# harp_timestamp_generator_Gen3.net
KiCad netlist of a schematic drawn in EAGLE
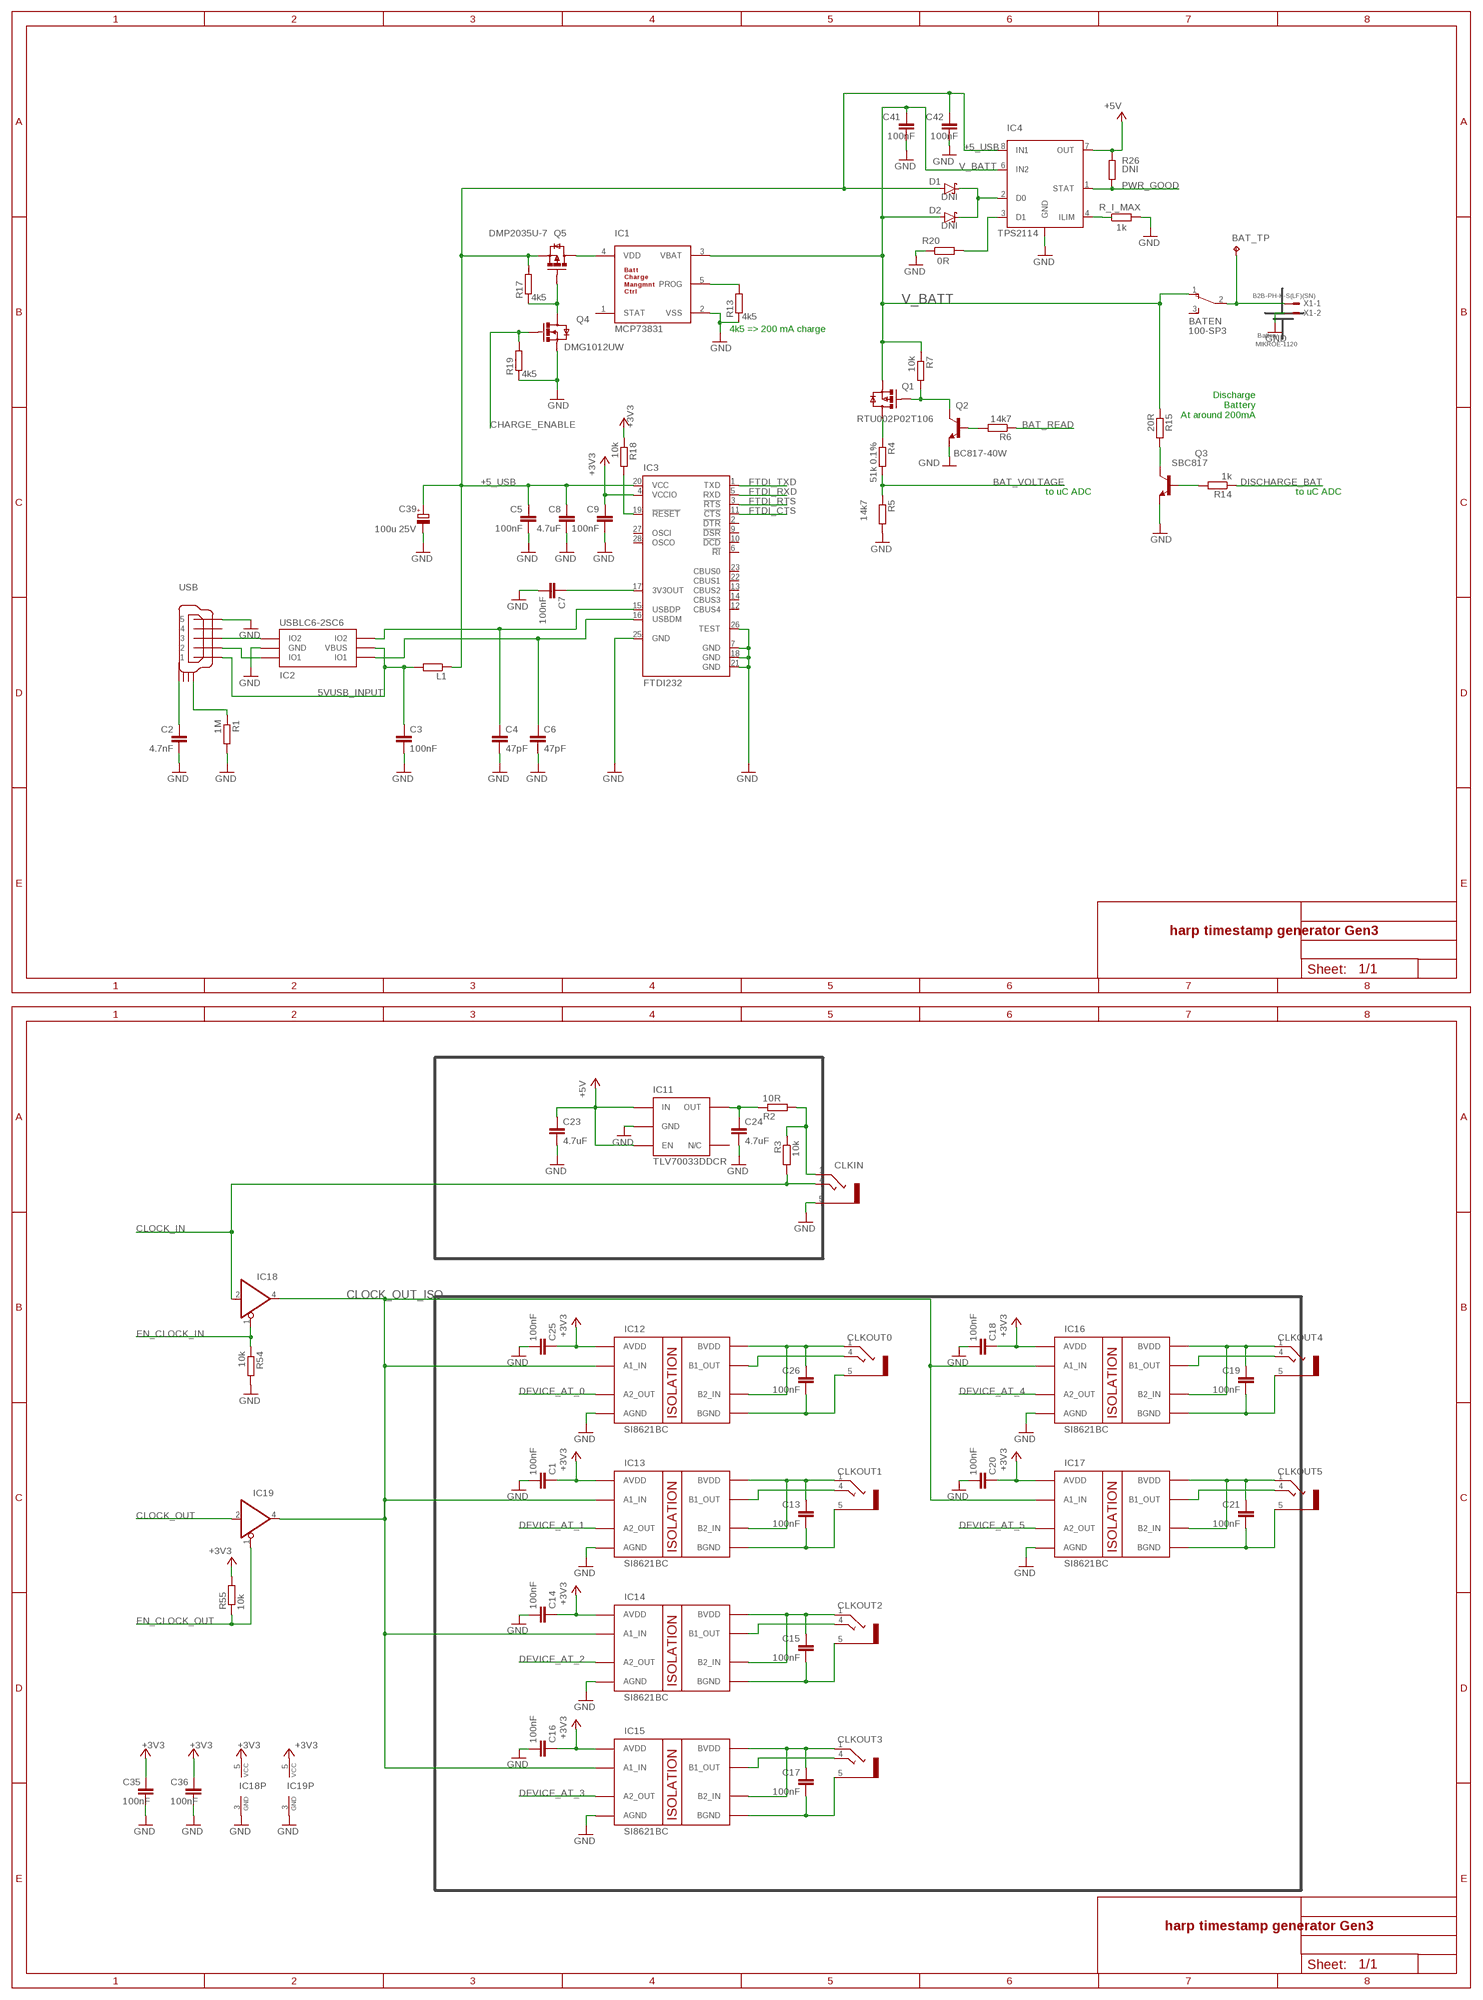
[diagram p0: schematic, sheet 1, part 1 of 2]
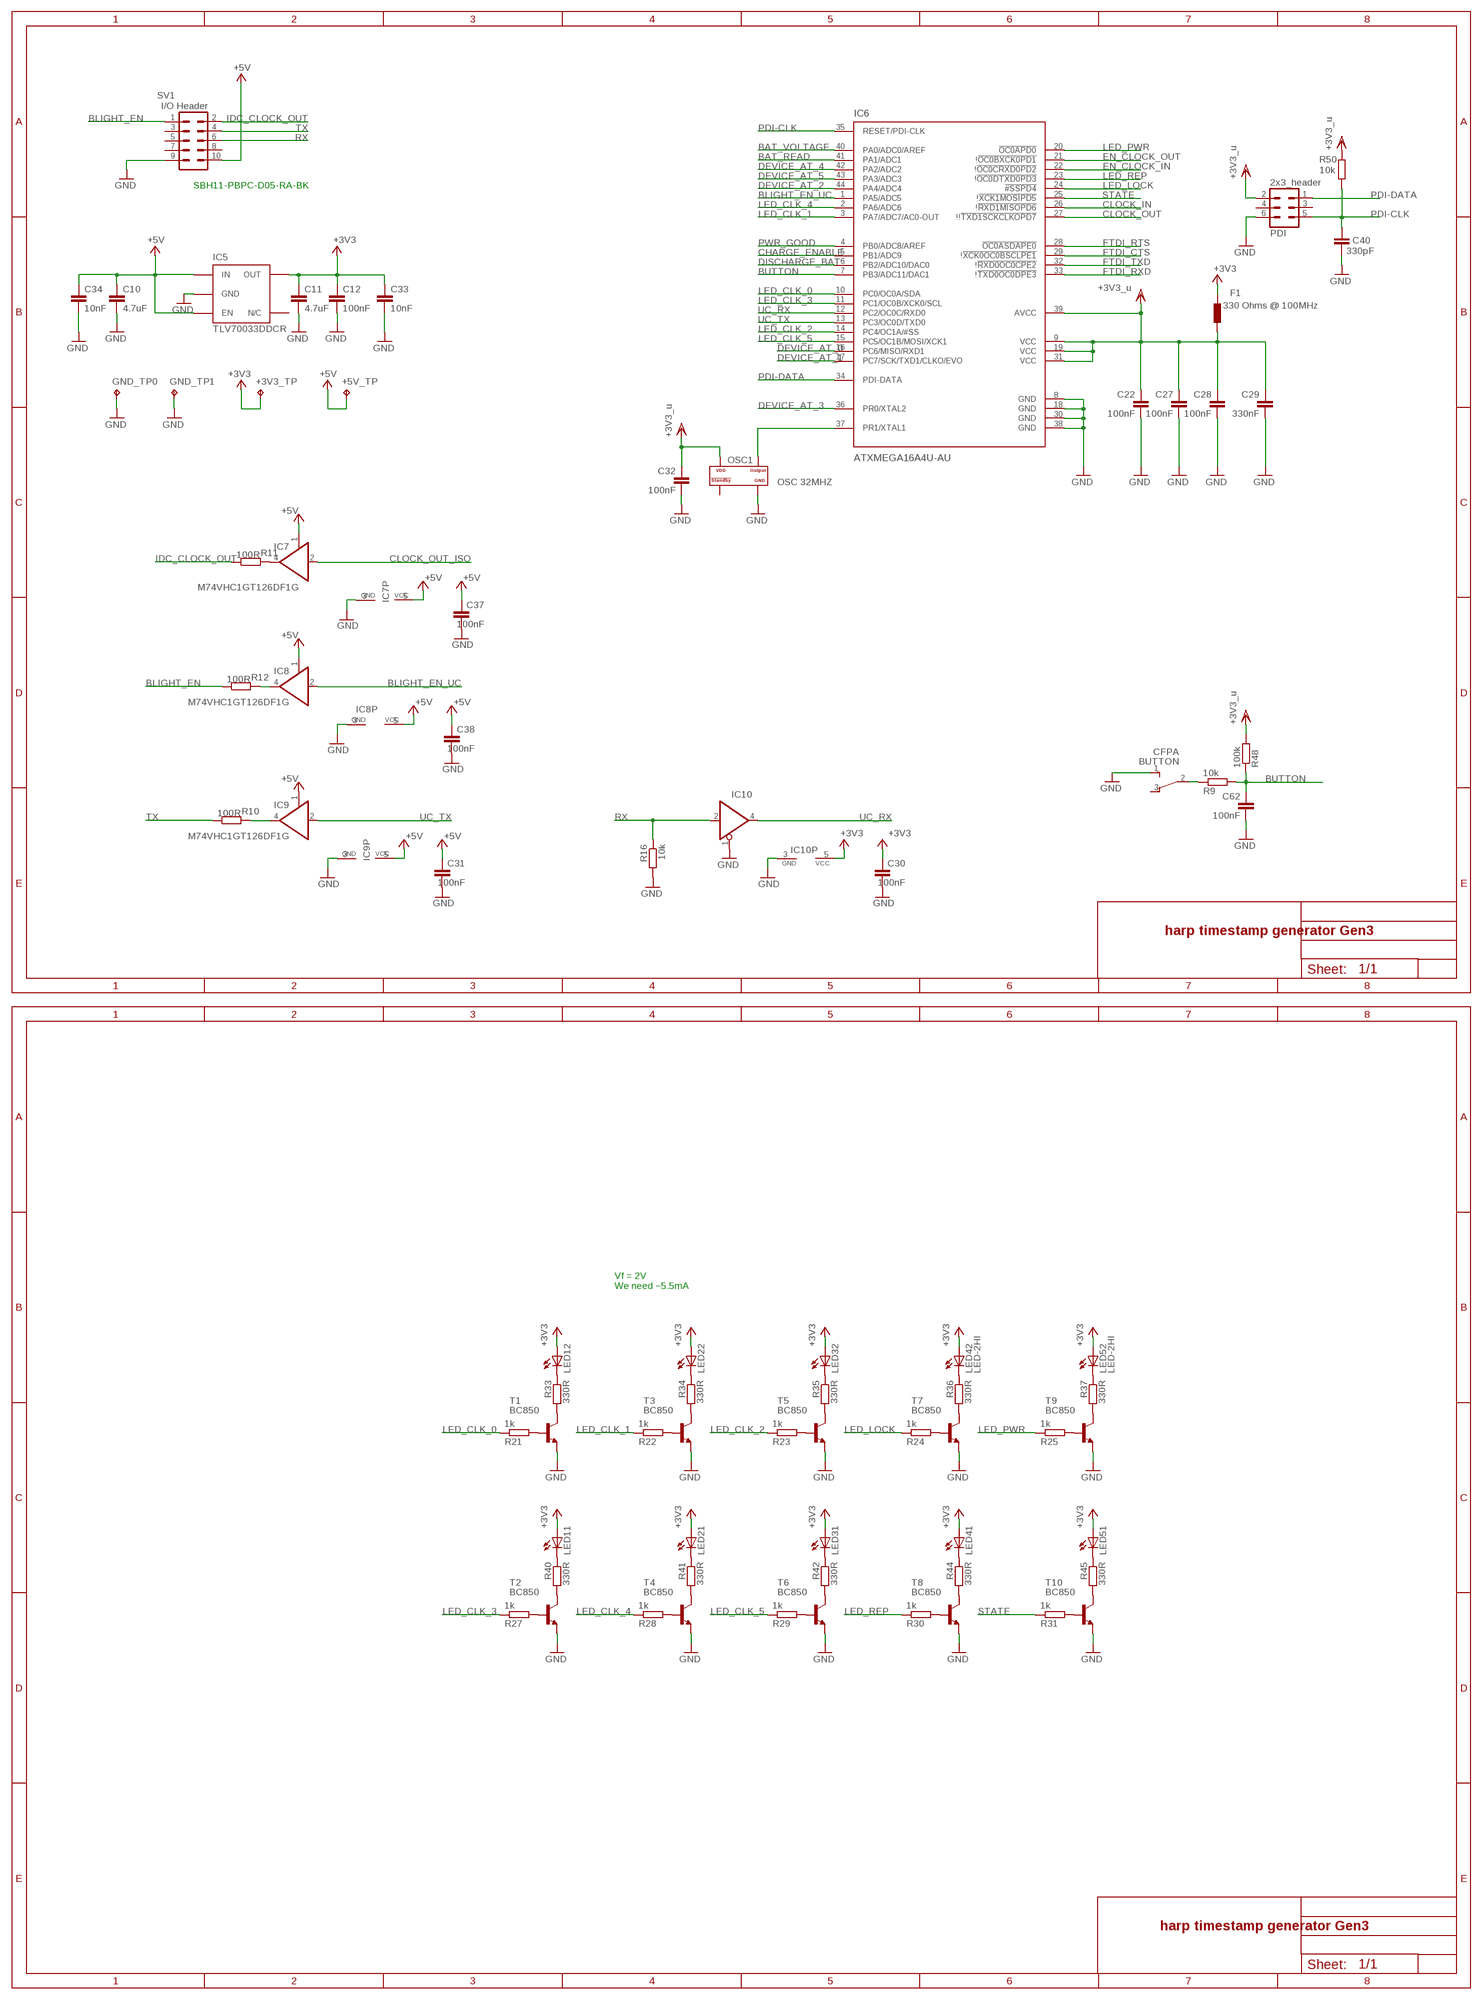
[diagram p1: schematic, sheet 1, part 2 of 2]

(export (version "E")
  (design (tool "Eeschema 10.0.6"))
  (components
    (comp (ref "+3V3_TP")
      (value "TPPAD1-13")
      (footprint "eagle-import:P1-13")
      (fields (field (name "MPN") "n.a."))
      (libsource (lib "eagle-import") (part "TPPAD1-13"))
    )
    (comp (ref "+5V_TP")
      (value "TPPAD1-13")
      (footprint "eagle-import:P1-13")
      (fields (field (name "MPN") "n.a."))
      (libsource (lib "eagle-import") (part "TPPAD1-13"))
    )
    (comp (ref "BATEN")
      (value "100-SP3")
      (footprint "eagle-import:2M1-SP1-T2-B4-M6RE")
      (fields (field (name "MPN") "7101MD9ABE"))
      (libsource (lib "eagle-import") (part "SPDT_2M-WITHOFF"))
    )
    (comp (ref "BAT_TP")
      (value "TPPAD1-13")
      (footprint "eagle-import:P1-13")
      (fields (field (name "MPN") "n.a."))
      (libsource (lib "eagle-import") (part "TPPAD1-13"))
    )
    (comp (ref "BUTTON")
      (value "CFPA")
      (footprint "eagle-import:CFPA")
      (fields (field (name "MPN") "CFPA-1FB4-A2T"))
      (libsource (lib "eagle-import") (part "harp timestamp generator Gen3_SPDT_CFPA"))
    )
    (comp (ref "C1")
      (value "100nF")
      (footprint "eagle-import:C0402")
      (fields (field (name "MPN") "CGA2B3X7R1H104K050BB"))
      (libsource (lib "eagle-import") (part "C-EUC0402"))
    )
    (comp (ref "C2")
      (value "4.7nF")
      (footprint "eagle-import:C0402")
      (fields (field (name "MPN") "UMK105B7472KV-F"))
      (libsource (lib "eagle-import") (part "C-EUC0402"))
    )
    (comp (ref "C3")
      (value "100nF")
      (footprint "eagle-import:C0402")
      (fields (field (name "MPN") "CGA2B3X7R1H104K050BB"))
      (libsource (lib "eagle-import") (part "C-EUC0402"))
    )
    (comp (ref "C4")
      (value "47pF")
      (footprint "eagle-import:C0402")
      (fields (field (name "MPN") "04025A470JAT2A"))
      (libsource (lib "eagle-import") (part "C-EUC0402"))
    )
    (comp (ref "C5")
      (value "100nF")
      (footprint "eagle-import:C0402")
      (fields (field (name "MPN") "CGA2B3X7R1H104K050BB"))
      (libsource (lib "eagle-import") (part "C-EUC0402"))
    )
    (comp (ref "C6")
      (value "47pF")
      (footprint "eagle-import:C0402")
      (fields (field (name "MPN") "04025A470JAT2A"))
      (libsource (lib "eagle-import") (part "C-EUC0402"))
    )
    (comp (ref "C7")
      (value "100nF")
      (footprint "eagle-import:C0402")
      (fields (field (name "MPN") "CGA2B3X7R1H104K050BB"))
      (libsource (lib "eagle-import") (part "C-EUC0402"))
    )
    (comp (ref "C8")
      (value "4.7uF")
      (footprint "eagle-import:C0603")
      (fields (field (name "MPN") "EMK107ABJ475KA-T"))
      (libsource (lib "eagle-import") (part "C-EUC0603"))
    )
    (comp (ref "C9")
      (value "100nF")
      (footprint "eagle-import:C0402")
      (fields (field (name "MPN") "CGA2B3X7R1H104K050BB"))
      (libsource (lib "eagle-import") (part "C-EUC0402"))
    )
    (comp (ref "C10")
      (value "4.7uF")
      (footprint "eagle-import:C0603")
      (fields (field (name "MPN") "EMK107ABJ475KA-T"))
      (libsource (lib "eagle-import") (part "C-EUC0603"))
    )
    (comp (ref "C11")
      (value "4.7uF")
      (footprint "eagle-import:C0603")
      (fields (field (name "MPN") "EMK107ABJ475KA-T"))
      (libsource (lib "eagle-import") (part "C-EUC0603"))
    )
    (comp (ref "C12")
      (value "100nF")
      (footprint "eagle-import:C0402")
      (fields (field (name "MPN") "CGA2B3X7R1H104K050BB"))
      (libsource (lib "eagle-import") (part "C-EUC0402"))
    )
    (comp (ref "C13")
      (value "100nF")
      (footprint "eagle-import:C0402")
      (fields (field (name "MPN") "CGA2B3X7R1H104K050BB"))
      (libsource (lib "eagle-import") (part "C-EUC0402"))
    )
    (comp (ref "C14")
      (value "100nF")
      (footprint "eagle-import:C0402")
      (fields (field (name "MPN") "CGA2B3X7R1H104K050BB"))
      (libsource (lib "eagle-import") (part "C-EUC0402"))
    )
    (comp (ref "C15")
      (value "100nF")
      (footprint "eagle-import:C0402")
      (fields (field (name "MPN") "CGA2B3X7R1H104K050BB"))
      (libsource (lib "eagle-import") (part "C-EUC0402"))
    )
    (comp (ref "C16")
      (value "100nF")
      (footprint "eagle-import:C0402")
      (fields (field (name "MPN") "CGA2B3X7R1H104K050BB"))
      (libsource (lib "eagle-import") (part "C-EUC0402"))
    )
    (comp (ref "C17")
      (value "100nF")
      (footprint "eagle-import:C0402")
      (fields (field (name "MPN") "CGA2B3X7R1H104K050BB"))
      (libsource (lib "eagle-import") (part "C-EUC0402"))
    )
    (comp (ref "C18")
      (value "100nF")
      (footprint "eagle-import:C0402")
      (fields (field (name "MPN") "CGA2B3X7R1H104K050BB"))
      (libsource (lib "eagle-import") (part "C-EUC0402"))
    )
    (comp (ref "C19")
      (value "100nF")
      (footprint "eagle-import:C0402")
      (fields (field (name "MPN") "CGA2B3X7R1H104K050BB"))
      (libsource (lib "eagle-import") (part "C-EUC0402"))
    )
    (comp (ref "C20")
      (value "100nF")
      (footprint "eagle-import:C0402")
      (fields (field (name "MPN") "CGA2B3X7R1H104K050BB"))
      (libsource (lib "eagle-import") (part "C-EUC0402"))
    )
    (comp (ref "C21")
      (value "100nF")
      (footprint "eagle-import:C0402")
      (fields (field (name "MPN") "CGA2B3X7R1H104K050BB"))
      (libsource (lib "eagle-import") (part "C-EUC0402"))
    )
    (comp (ref "C22")
      (value "100nF")
      (footprint "eagle-import:C0402")
      (fields (field (name "MPN") "CGA2B3X7R1H104K050BB"))
      (libsource (lib "eagle-import") (part "C-EUC0402"))
    )
    (comp (ref "C23")
      (value "4.7uF")
      (footprint "eagle-import:C0603")
      (fields (field (name "MPN") "EMK107ABJ475KA-T"))
      (libsource (lib "eagle-import") (part "C-EUC0603"))
    )
    (comp (ref "C24")
      (value "4.7uF")
      (footprint "eagle-import:C0603")
      (fields (field (name "MPN") "EMK107ABJ475KA-T"))
      (libsource (lib "eagle-import") (part "C-EUC0603"))
    )
    (comp (ref "C25")
      (value "100nF")
      (footprint "eagle-import:C0402")
      (fields (field (name "MPN") "CGA2B3X7R1H104K050BB"))
      (libsource (lib "eagle-import") (part "C-EUC0402"))
    )
    (comp (ref "C26")
      (value "100nF")
      (footprint "eagle-import:C0402")
      (fields (field (name "MPN") "CGA2B3X7R1H104K050BB"))
      (libsource (lib "eagle-import") (part "C-EUC0402"))
    )
    (comp (ref "C27")
      (value "100nF")
      (footprint "eagle-import:C0402")
      (fields (field (name "MPN") "CGA2B3X7R1H104K050BB"))
      (libsource (lib "eagle-import") (part "C-EUC0402"))
    )
    (comp (ref "C28")
      (value "100nF")
      (footprint "eagle-import:C0402")
      (fields (field (name "MPN") "CGA2B3X7R1H104K050BB"))
      (libsource (lib "eagle-import") (part "C-EUC0402"))
    )
    (comp (ref "C29")
      (value "330nF")
      (footprint "eagle-import:C0402")
      (fields (field (name "MPN") "GRM155R61A334KE15D"))
      (libsource (lib "eagle-import") (part "C-EUC0402"))
    )
    (comp (ref "C30")
      (value "100nF")
      (footprint "eagle-import:C0402")
      (fields (field (name "MPN") "CGA2B3X7R1H104K050BB"))
      (libsource (lib "eagle-import") (part "C-EUC0402"))
    )
    (comp (ref "C31")
      (value "100nF")
      (footprint "eagle-import:C0402")
      (fields (field (name "MPN") "CGA2B3X7R1H104K050BB"))
      (libsource (lib "eagle-import") (part "C-EUC0402"))
    )
    (comp (ref "C32")
      (value "100nF")
      (footprint "eagle-import:C0402")
      (fields (field (name "MPN") "CGA2B3X7R1H104K050BB"))
      (libsource (lib "eagle-import") (part "C-EUC0402"))
    )
    (comp (ref "C33")
      (value "10nF")
      (footprint "eagle-import:C0402")
      (fields (field (name "MPN") "CL05B103KB5NNNC"))
      (libsource (lib "eagle-import") (part "C-EUC0402"))
    )
    (comp (ref "C34")
      (value "10nF")
      (footprint "eagle-import:C0402")
      (fields (field (name "MPN") "CL05B103KB5NNNC"))
      (libsource (lib "eagle-import") (part "C-EUC0402"))
    )
    (comp (ref "C35")
      (value "100nF")
      (footprint "eagle-import:C0402")
      (fields (field (name "MPN") "CGA2B3X7R1H104K050BB"))
      (libsource (lib "eagle-import") (part "C-EUC0402"))
    )
    (comp (ref "C36")
      (value "100nF")
      (footprint "eagle-import:C0402")
      (fields (field (name "MPN") "CGA2B3X7R1H104K050BB"))
      (libsource (lib "eagle-import") (part "C-EUC0402"))
    )
    (comp (ref "C37")
      (value "100nF")
      (footprint "eagle-import:C0402")
      (fields (field (name "MPN") "CGA2B3X7R1H104K050BB"))
      (libsource (lib "eagle-import") (part "C-EUC0402"))
    )
    (comp (ref "C38")
      (value "100nF")
      (footprint "eagle-import:C0402")
      (fields (field (name "MPN") "CGA2B3X7R1H104K050BB"))
      (libsource (lib "eagle-import") (part "C-EUC0402"))
    )
    (comp (ref "C39")
      (value "100u 25V")
      (footprint "eagle-import:TT2D6")
      (fields (field (name "MPN") "EEUFM1E101B"))
      (libsource (lib "eagle-import") (part "CPOL-EUTT2D6"))
    )
    (comp (ref "C40")
      (value "330pF")
      (footprint "eagle-import:C0402")
      (fields (field (name "MPN") "C0402C331JAGAC7867"))
      (libsource (lib "eagle-import") (part "C-EUC0402"))
    )
    (comp (ref "C41")
      (value "100nF")
      (footprint "eagle-import:C0402")
      (fields (field (name "MPN") "CGA2B3X7R1H104K050BB"))
      (libsource (lib "eagle-import") (part "C-EUC0402"))
    )
    (comp (ref "C42")
      (value "100nF")
      (footprint "eagle-import:C0402")
      (fields (field (name "MPN") "CGA2B3X7R1H104K050BB"))
      (libsource (lib "eagle-import") (part "C-EUC0402"))
    )
    (comp (ref "C62")
      (value "100nF")
      (footprint "eagle-import:C0402")
      (fields (field (name "MPN") "CGA2B3X7R1H104K050BB"))
      (libsource (lib "eagle-import") (part "C-EUC0402"))
    )
    (comp (ref "CLKIN")
      (value "CLCK_JACK")
      (footprint "eagle-import:35RASMT2BHNTRX")
      (fields (field (name "MPN") "35RASMT2BHNTRX"))
      (libsource (lib "eagle-import") (part "STEREO_JACK"))
    )
    (comp (ref "CLKOUT0")
      (value "CLCK_JACK")
      (footprint "eagle-import:35RASMT2BHNTRX")
      (fields (field (name "MPN") "35RASMT2BHNTRX"))
      (libsource (lib "eagle-import") (part "STEREO_JACK"))
    )
    (comp (ref "CLKOUT1")
      (value "CLCK_JACK")
      (footprint "eagle-import:35RASMT2BHNTRX")
      (fields (field (name "MPN") "35RASMT2BHNTRX"))
      (libsource (lib "eagle-import") (part "STEREO_JACK"))
    )
    (comp (ref "CLKOUT2")
      (value "CLCK_JACK")
      (footprint "eagle-import:35RASMT2BHNTRX")
      (fields (field (name "MPN") "35RASMT2BHNTRX"))
      (libsource (lib "eagle-import") (part "STEREO_JACK"))
    )
    (comp (ref "CLKOUT3")
      (value "CLCK_JACK")
      (footprint "eagle-import:35RASMT2BHNTRX")
      (fields (field (name "MPN") "35RASMT2BHNTRX"))
      (libsource (lib "eagle-import") (part "STEREO_JACK"))
    )
    (comp (ref "CLKOUT4")
      (value "CLCK_JACK")
      (footprint "eagle-import:35RASMT2BHNTRX")
      (fields (field (name "MPN") "35RASMT2BHNTRX"))
      (libsource (lib "eagle-import") (part "STEREO_JACK"))
    )
    (comp (ref "CLKOUT5")
      (value "CLCK_JACK")
      (footprint "eagle-import:35RASMT2BHNTRX")
      (fields (field (name "MPN") "35RASMT2BHNTRX"))
      (libsource (lib "eagle-import") (part "STEREO_JACK"))
    )
    (comp (ref "D1")
      (value "DNI")
      (footprint "eagle-import:SOD3715X135")
      (libsource (lib "eagle-import") (part "MBRM120"))
    )
    (comp (ref "D2")
      (value "DNI")
      (footprint "eagle-import:SOD3715X135")
      (libsource (lib "eagle-import") (part "MBRM120"))
    )
    (comp (ref "F1")
      (value "330 Ohms @ 100MHz")
      (footprint "eagle-import:R0603")
      (fields (field (name "MPN") "BLM18SG331TN1D"))
      (libsource (lib "eagle-import") (part "BLM15HF0603"))
    )
    (comp (ref "GND_TP0")
      (value "TPPAD1-13")
      (footprint "eagle-import:P1-13")
      (fields (field (name "MPN") "n.a."))
      (libsource (lib "eagle-import") (part "TPPAD1-13"))
    )
    (comp (ref "GND_TP1")
      (value "TPPAD1-13")
      (footprint "eagle-import:P1-13")
      (fields (field (name "MPN") "n.a."))
      (libsource (lib "eagle-import") (part "TPPAD1-13"))
    )
    (comp (ref "IC1")
      (value "MCP73831")
      (footprint "eagle-import:TSOT23-5")
      (fields (field (name "MPN") "MCP73831T-2ATI/OT"))
      (libsource (lib "eagle-import") (part "MCP73831T-2ATI/OT"))
    )
    (comp (ref "IC2")
      (value "USBLC6-2SC6")
      (footprint "eagle-import:SOT23-6L")
      (libsource (lib "eagle-import") (part "USBLC6-2"))
    )
    (comp (ref "IC3")
      (value "FTDI232")
      (footprint "eagle-import:SSOP28")
      (fields (field (name "MPN") "FT232RL-REEL"))
      (libsource (lib "eagle-import") (part "FT232RL"))
    )
    (comp (ref "IC4")
      (value "TPS2114")
      (footprint "eagle-import:TSSOP8")
      (fields (field (name "MPN") "TPS2114APWR"))
      (libsource (lib "eagle-import") (part "TPS2114"))
    )
    (comp (ref "IC5")
      (value "TLV70033DDCR")
      (footprint "eagle-import:TSOT23-5")
      (libsource (lib "eagle-import") (part "TLV700XX"))
    )
    (comp (ref "IC6")
      (value "ATXMEGA16A4U-AU")
      (footprint "eagle-import:QFP80P1200X1200X120-44N")
      (libsource (lib "eagle-import") (part "AT-XMEGA-XXA4-AU"))
    )
    (comp (ref "IC7")
      (value "M74VHC1GT126DF1G")
      (footprint "eagle-import:SC70-5")
      (fields (field (name "MPN") "M74VHC1GT126DF1G"))
      (libsource (lib "eagle-import") (part "741G126DCKAHC"))
    )
    (comp (ref "IC8")
      (value "M74VHC1GT126DF1G")
      (footprint "eagle-import:SC70-5")
      (fields (field (name "MPN") "M74VHC1GT126DF1G"))
      (libsource (lib "eagle-import") (part "741G126DCKAHC"))
    )
    (comp (ref "IC9")
      (value "M74VHC1GT126DF1G")
      (footprint "eagle-import:SC70-5")
      (fields (field (name "MPN") "M74VHC1GT126DF1G"))
      (libsource (lib "eagle-import") (part "741G126DCKAHC"))
    )
    (comp (ref "IC10")
      (value "SN74LVC1G125DBVT")
      (footprint "eagle-import:SOT23-5")
      (fields (field (name "MPN") "SN74LVC1G125DBVT"))
      (libsource (lib "eagle-import") (part "741G125DBVAHC"))
    )
    (comp (ref "IC11")
      (value "TLV70033DDCR")
      (footprint "eagle-import:TSOT23-5")
      (libsource (lib "eagle-import") (part "TLV700XX"))
    )
    (comp (ref "IC12")
      (value "SI8621BC")
      (footprint "eagle-import:SOIC8")
      (fields (field (name "MPN") "Si8621BC-B-IS"))
      (libsource (lib "eagle-import") (part "SI8621BC-B-IS"))
    )
    (comp (ref "IC13")
      (value "SI8621BC")
      (footprint "eagle-import:SOIC8")
      (fields (field (name "MPN") "Si8621BC-B-IS"))
      (libsource (lib "eagle-import") (part "SI8621BC-B-IS"))
    )
    (comp (ref "IC14")
      (value "SI8621BC")
      (footprint "eagle-import:SOIC8")
      (fields (field (name "MPN") "Si8621BC-B-IS"))
      (libsource (lib "eagle-import") (part "SI8621BC-B-IS"))
    )
    (comp (ref "IC15")
      (value "SI8621BC")
      (footprint "eagle-import:SOIC8")
      (fields (field (name "MPN") "Si8621BC-B-IS"))
      (libsource (lib "eagle-import") (part "SI8621BC-B-IS"))
    )
    (comp (ref "IC16")
      (value "SI8621BC")
      (footprint "eagle-import:SOIC8")
      (fields (field (name "MPN") "Si8621BC-B-IS"))
      (libsource (lib "eagle-import") (part "SI8621BC-B-IS"))
    )
    (comp (ref "IC17")
      (value "SI8621BC")
      (footprint "eagle-import:SOIC8")
      (fields (field (name "MPN") "Si8621BC-B-IS"))
      (libsource (lib "eagle-import") (part "SI8621BC-B-IS"))
    )
    (comp (ref "IC18")
      (value "SN74LVC1G125DBVT")
      (footprint "eagle-import:SOT23-5")
      (fields (field (name "MPN") "SN74LVC1G125DBVT"))
      (libsource (lib "eagle-import") (part "741G125DBVAHC"))
    )
    (comp (ref "IC19")
      (value "SN74LVC1G125DBVT")
      (footprint "eagle-import:SOT23-5")
      (fields (field (name "MPN") "SN74LVC1G125DBVT"))
      (libsource (lib "eagle-import") (part "741G125DBVAHC"))
    )
    (comp (ref "L1")
      (value "40R@100MHz")
      (footprint "eagle-import:R0805")
      (fields (field (name "MPN") "MI0805K400R-10"))
      (libsource (lib "eagle-import") (part "R-EU_R0805"))
    )
    (comp (ref "LED1")
      (value "LED-2HI")
      (footprint "eagle-import:569-011X-X00_LED_ARRAY")
      (fields (field (name "MPN") "5690111100F"))
      (libsource (lib "eagle-import") (part "LED_2X_VERTICAL"))
    )
    (comp (ref "LED2")
      (value "LED-2HI")
      (footprint "eagle-import:569-011X-X00_LED_ARRAY")
      (fields (field (name "MPN") "5690111100F"))
      (libsource (lib "eagle-import") (part "LED_2X_VERTICAL"))
    )
    (comp (ref "LED3")
      (value "LED-2HI")
      (footprint "eagle-import:569-011X-X00_LED_ARRAY")
      (fields (field (name "MPN") "5690111100F"))
      (libsource (lib "eagle-import") (part "LED_2X_VERTICAL"))
    )
    (comp (ref "LED4")
      (value "LED-2HI")
      (footprint "eagle-import:569-011X-X00_LED_ARRAY")
      (fields (field (name "MPN") "5690111100F"))
      (libsource (lib "eagle-import") (part "LED_2X_VERTICAL"))
    )
    (comp (ref "LED5")
      (value "LED-2HI")
      (footprint "eagle-import:569-011X-X00_LED_ARRAY")
      (fields (field (name "MPN") "5690111100F"))
      (libsource (lib "eagle-import") (part "LED_2X_VERTICAL"))
    )
    (comp (ref "OSC1")
      (value "OSC 32MHZ")
      (footprint "eagle-import:OSCILLATOR_3.2X2.5")
      (fields (field (name "MPN") "O 32,0-JT32C-A-K-3,3-LF"))
      (libsource (lib "eagle-import") (part "OSCILLATOR"))
    )
    (comp (ref "PDI")
      (value "2x3_header")
      (footprint "eagle-import:MA03-2")
      (fields (field (name "MPN") "67996-206HLF"))
      (libsource (lib "eagle-import") (part "MA03-2"))
    )
    (comp (ref "Q1")
      (value "RTU002P02T106")
      (footprint "eagle-import:SOT323")
      (libsource (lib "eagle-import") (part "MOSFET-PCHANNEL-ROHM"))
    )
    (comp (ref "Q2")
      (value "BC817-40W")
      (footprint "eagle-import:SOT323-BEC")
      (fields (field (name "MPN") "BC817-40W,135"))
      (libsource (lib "eagle-import") (part "BC817"))
    )
    (comp (ref "Q3")
      (value "SBC817")
      (footprint "eagle-import:SOT23-BEC")
      (fields (field (name "MPN") "SBC817-40LT1G"))
      (libsource (lib "eagle-import") (part "BC817SMD-40LT1"))
    )
    (comp (ref "Q4")
      (value "DMG1012UW")
      (footprint "eagle-import:SOT323")
      (fields (field (name "MPN") "DMG1012UW-7"))
      (libsource (lib "eagle-import") (part "DMG1012UW"))
    )
    (comp (ref "Q5")
      (value "DMP2035U-7")
      (footprint "eagle-import:SOT323")
      (libsource (lib "eagle-import") (part "DMP2035U-7"))
    )
    (comp (ref "R1")
      (value "1M")
      (footprint "eagle-import:R0402")
      (fields (field (name "MPN") "CRCW04021M00FKEDC"))
      (libsource (lib "eagle-import") (part "R-EU_R0402"))
    )
    (comp (ref "R2")
      (value "10R")
      (footprint "eagle-import:R0402")
      (fields (field (name "MPN") "CRCW040210R0FKEDHP"))
      (libsource (lib "eagle-import") (part "R-EU_R0402"))
    )
    (comp (ref "R3")
      (value "10k")
      (footprint "eagle-import:R0402")
      (fields (field (name "MPN") "RMCF0402FT10K0"))
      (libsource (lib "eagle-import") (part "R-EU_R0402"))
    )
    (comp (ref "R4")
      (value "51k 0.1%")
      (footprint "eagle-import:R0402")
      (fields (field (name "MPN") "ERA-2AEB513X"))
      (libsource (lib "eagle-import") (part "R-EU_R0402"))
    )
    (comp (ref "R5")
      (value "14k7")
      (footprint "eagle-import:R0402")
      (fields (field (name "MPN") "RT0402BRD0714K7L"))
      (libsource (lib "eagle-import") (part "R-EU_R0402"))
    )
    (comp (ref "R6")
      (value "14k7")
      (footprint "eagle-import:R0402")
      (fields (field (name "MPN") "RT0402BRD0714K7L"))
      (libsource (lib "eagle-import") (part "R-EU_R0402"))
    )
    (comp (ref "R7")
      (value "10k")
      (footprint "eagle-import:R0402")
      (fields (field (name "MPN") "RMCF0402FT10K0"))
      (libsource (lib "eagle-import") (part "R-EU_R0402"))
    )
    (comp (ref "R9")
      (value "10k")
      (footprint "eagle-import:R0402")
      (fields (field (name "MPN") "RMCF0402FT10K0"))
      (libsource (lib "eagle-import") (part "R-EU_R0402"))
    )
    (comp (ref "R10")
      (value "100R")
      (footprint "eagle-import:R0603")
      (fields (field (name "MPN") "RT0603DRD07100RL"))
      (libsource (lib "eagle-import") (part "R-EU_R0603"))
    )
    (comp (ref "R11")
      (value "100R")
      (footprint "eagle-import:R0603")
      (fields (field (name "MPN") "RT0603DRD07100RL"))
      (libsource (lib "eagle-import") (part "R-EU_R0603"))
    )
    (comp (ref "R12")
      (value "100R")
      (footprint "eagle-import:R0603")
      (fields (field (name "MPN") "RT0603DRD07100RL"))
      (libsource (lib "eagle-import") (part "R-EU_R0603"))
    )
    (comp (ref "R13")
      (value "4k5")
      (footprint "eagle-import:R0402")
      (fields (field (name "MPN") "RT0402BRD074K53L"))
      (libsource (lib "eagle-import") (part "R-EU_R0402"))
    )
    (comp (ref "R14")
      (value "1k")
      (footprint "eagle-import:R0402")
      (fields (field (name "MPN") "RMCF0402FT1K00"))
      (libsource (lib "eagle-import") (part "R-EU_R0402"))
    )
    (comp (ref "R15")
      (value "20R")
      (footprint "eagle-import:R2512")
      (fields (field (name "MPN") "RCP2512W25R0GEB"))
      (libsource (lib "eagle-import") (part "R-EU_R2512"))
    )
    (comp (ref "R16")
      (value "10k")
      (footprint "eagle-import:R0402")
      (fields (field (name "MPN") "RMCF0402FT10K0"))
      (libsource (lib "eagle-import") (part "R-EU_R0402"))
    )
    (comp (ref "R17")
      (value "4k5")
      (footprint "eagle-import:R0402")
      (fields (field (name "MPN") "RT0402BRD074K53L"))
      (libsource (lib "eagle-import") (part "R-EU_R0402"))
    )
    (comp (ref "R18")
      (value "10k")
      (footprint "eagle-import:R0402")
      (fields (field (name "MPN") "RMCF0402FT10K0"))
      (libsource (lib "eagle-import") (part "R-EU_R0402"))
    )
    (comp (ref "R19")
      (value "4k5")
      (footprint "eagle-import:R0402")
      (fields (field (name "MPN") "RT0402BRD074K53L"))
      (libsource (lib "eagle-import") (part "R-EU_R0402"))
    )
    (comp (ref "R20")
      (value "0R")
      (footprint "eagle-import:R0402")
      (fields (field (name "MPN") "RMCF0402ZT0R00"))
      (libsource (lib "eagle-import") (part "R-EU_R0402"))
    )
    (comp (ref "R21")
      (value "1k")
      (footprint "eagle-import:R0402")
      (fields (field (name "MPN") "RMCF0402FT1K00"))
      (libsource (lib "eagle-import") (part "R-EU_R0402"))
    )
    (comp (ref "R22")
      (value "1k")
      (footprint "eagle-import:R0402")
      (fields (field (name "MPN") "RMCF0402FT1K00"))
      (libsource (lib "eagle-import") (part "R-EU_R0402"))
    )
    (comp (ref "R23")
      (value "1k")
      (footprint "eagle-import:R0402")
      (fields (field (name "MPN") "RMCF0402FT1K00"))
      (libsource (lib "eagle-import") (part "R-EU_R0402"))
    )
    (comp (ref "R24")
      (value "1k")
      (footprint "eagle-import:R0402")
      (fields (field (name "MPN") "RMCF0402FT1K00"))
      (libsource (lib "eagle-import") (part "R-EU_R0402"))
    )
    (comp (ref "R25")
      (value "1k")
      (footprint "eagle-import:R0402")
      (fields (field (name "MPN") "RMCF0402FT1K00"))
      (libsource (lib "eagle-import") (part "R-EU_R0402"))
    )
    (comp (ref "R26")
      (value "DNI")
      (footprint "eagle-import:R0402")
      (libsource (lib "eagle-import") (part "R-EU_R0402"))
    )
    (comp (ref "R27")
      (value "1k")
      (footprint "eagle-import:R0402")
      (fields (field (name "MPN") "RMCF0402FT1K00"))
      (libsource (lib "eagle-import") (part "R-EU_R0402"))
    )
    (comp (ref "R28")
      (value "1k")
      (footprint "eagle-import:R0402")
      (fields (field (name "MPN") "RMCF0402FT1K00"))
      (libsource (lib "eagle-import") (part "R-EU_R0402"))
    )
    (comp (ref "R29")
      (value "1k")
      (footprint "eagle-import:R0402")
      (fields (field (name "MPN") "RMCF0402FT1K00"))
      (libsource (lib "eagle-import") (part "R-EU_R0402"))
    )
    (comp (ref "R30")
      (value "1k")
      (footprint "eagle-import:R0402")
      (fields (field (name "MPN") "RMCF0402FT1K00"))
      (libsource (lib "eagle-import") (part "R-EU_R0402"))
    )
    (comp (ref "R31")
      (value "1k")
      (footprint "eagle-import:R0402")
      (fields (field (name "MPN") "RMCF0402FT1K00"))
      (libsource (lib "eagle-import") (part "R-EU_R0402"))
    )
    (comp (ref "R33")
      (value "330R")
      (footprint "eagle-import:R0402")
      (fields (field (name "MPN") "RC0402FR-07330RL "))
      (libsource (lib "eagle-import") (part "R-EU_R0402"))
    )
    (comp (ref "R34")
      (value "330R")
      (footprint "eagle-import:R0402")
      (fields (field (name "MPN") "RC0402FR-07330RL "))
      (libsource (lib "eagle-import") (part "R-EU_R0402"))
    )
    (comp (ref "R35")
      (value "330R")
      (footprint "eagle-import:R0402")
      (fields (field (name "MPN") "RC0402FR-07330RL "))
      (libsource (lib "eagle-import") (part "R-EU_R0402"))
    )
    (comp (ref "R36")
      (value "330R")
      (footprint "eagle-import:R0402")
      (fields (field (name "MPN") "RC0402FR-07330RL "))
      (libsource (lib "eagle-import") (part "R-EU_R0402"))
    )
    (comp (ref "R37")
      (value "330R")
      (footprint "eagle-import:R0402")
      (fields (field (name "MPN") "RC0402FR-07330RL "))
      (libsource (lib "eagle-import") (part "R-EU_R0402"))
    )
    (comp (ref "R40")
      (value "330R")
      (footprint "eagle-import:R0402")
      (fields (field (name "MPN") "RC0402FR-07330RL "))
      (libsource (lib "eagle-import") (part "R-EU_R0402"))
    )
    (comp (ref "R41")
      (value "330R")
      (footprint "eagle-import:R0402")
      (fields (field (name "MPN") "RC0402FR-07330RL "))
      (libsource (lib "eagle-import") (part "R-EU_R0402"))
    )
    (comp (ref "R42")
      (value "330R")
      (footprint "eagle-import:R0402")
      (fields (field (name "MPN") "RC0402FR-07330RL "))
      (libsource (lib "eagle-import") (part "R-EU_R0402"))
    )
    (comp (ref "R44")
      (value "330R")
      (footprint "eagle-import:R0402")
      (fields (field (name "MPN") "RC0402FR-07330RL "))
      (libsource (lib "eagle-import") (part "R-EU_R0402"))
    )
    (comp (ref "R45")
      (value "330R")
      (footprint "eagle-import:R0402")
      (fields (field (name "MPN") "RC0402FR-07330RL "))
      (libsource (lib "eagle-import") (part "R-EU_R0402"))
    )
    (comp (ref "R48")
      (value "100k")
      (footprint "eagle-import:R0402")
      (fields (field (name "MPN") "ERJ-2RHD1002X"))
      (libsource (lib "eagle-import") (part "R-EU_R0402"))
    )
    (comp (ref "R50")
      (value "10k")
      (footprint "eagle-import:R0402")
      (fields (field (name "MPN") "RMCF0402FT10K0"))
      (libsource (lib "eagle-import") (part "R-EU_R0402"))
    )
    (comp (ref "R54")
      (value "10k")
      (footprint "eagle-import:R0402")
      (fields (field (name "MPN") "RMCF0402FT10K0"))
      (libsource (lib "eagle-import") (part "R-EU_R0402"))
    )
    (comp (ref "R55")
      (value "10k")
      (footprint "eagle-import:R0402")
      (fields (field (name "MPN") "RMCF0402FT10K0"))
      (libsource (lib "eagle-import") (part "R-EU_R0402"))
    )
    (comp (ref "R_I_MAX")
      (value "1k")
      (footprint "eagle-import:R0402")
      (fields (field (name "MPN") "RMCF0402FT1K00"))
      (libsource (lib "eagle-import") (part "R-EU_R0402"))
    )
    (comp (ref "SV1")
      (value "I/O Header")
      (footprint "eagle-import:ML10L")
      (fields (field (name "MPN") "SBH11-PBPC-D05-RA-BK"))
      (libsource (lib "eagle-import") (part "ML10L"))
    )
    (comp (ref "T1")
      (value "BC850")
      (footprint "eagle-import:SOT23")
      (fields (field (name "MPN") "BC850C,215"))
      (libsource (lib "eagle-import") (part "BC850"))
    )
    (comp (ref "T2")
      (value "BC850")
      (footprint "eagle-import:SOT23")
      (fields (field (name "MPN") "BC850C,215"))
      (libsource (lib "eagle-import") (part "BC850"))
    )
    (comp (ref "T3")
      (value "BC850")
      (footprint "eagle-import:SOT23")
      (fields (field (name "MPN") "BC850C,215"))
      (libsource (lib "eagle-import") (part "BC850"))
    )
    (comp (ref "T4")
      (value "BC850")
      (footprint "eagle-import:SOT23")
      (fields (field (name "MPN") "BC850C,215"))
      (libsource (lib "eagle-import") (part "BC850"))
    )
    (comp (ref "T5")
      (value "BC850")
      (footprint "eagle-import:SOT23")
      (fields (field (name "MPN") "BC850C,215"))
      (libsource (lib "eagle-import") (part "BC850"))
    )
    (comp (ref "T6")
      (value "BC850")
      (footprint "eagle-import:SOT23")
      (fields (field (name "MPN") "BC850C,215"))
      (libsource (lib "eagle-import") (part "BC850"))
    )
    (comp (ref "T7")
      (value "BC850")
      (footprint "eagle-import:SOT23")
      (fields (field (name "MPN") "BC850C,215"))
      (libsource (lib "eagle-import") (part "BC850"))
    )
    (comp (ref "T8")
      (value "BC850")
      (footprint "eagle-import:SOT23")
      (fields (field (name "MPN") "BC850C,215"))
      (libsource (lib "eagle-import") (part "BC850"))
    )
    (comp (ref "T9")
      (value "BC850")
      (footprint "eagle-import:SOT23")
      (fields (field (name "MPN") "BC850C,215"))
      (libsource (lib "eagle-import") (part "BC850"))
    )
    (comp (ref "T10")
      (value "BC850")
      (footprint "eagle-import:SOT23")
      (fields (field (name "MPN") "BC850C,215"))
      (libsource (lib "eagle-import") (part "BC850"))
    )
    (comp (ref "USB")
      (value "mini USB")
      (footprint "eagle-import:240-0002-1")
      (fields (field (name "MPN") "UX60-MB-5S8"))
      (libsource (lib "eagle-import") (part "USB_MINI_B"))
    )
    (comp (ref "X1")
      (value "B2B-PH-K-S(LF)(SN)")
      (footprint "eagle-import:JST-XH-02-PACKAGE-ROUND-PAD")
      (libsource (lib "eagle-import") (part "JST-XH-02-PIN-ROUND-PAD"))
    )
  )
  (nets
    (net (code "1") (name "+3V3") (class "Default")
      (node (ref "+3V3_TP") (pin "TP") (pinfunction "TP_TP") (pintype "input"))
      (node (ref "C1") (pin "1") (pinfunction "1_1") (pintype "passive"))
      (node (ref "C11") (pin "1") (pinfunction "1_1") (pintype "passive"))
      (node (ref "C12") (pin "1") (pinfunction "1_1") (pintype "passive"))
      (node (ref "C14") (pin "1") (pinfunction "1_1") (pintype "passive"))
      (node (ref "C16") (pin "1") (pinfunction "1_1") (pintype "passive"))
      (node (ref "C18") (pin "1") (pinfunction "1_1") (pintype "passive"))
      (node (ref "C20") (pin "1") (pinfunction "1_1") (pintype "passive"))
      (node (ref "C25") (pin "1") (pinfunction "1_1") (pintype "passive"))
      (node (ref "C30") (pin "1") (pinfunction "1_1") (pintype "passive"))
      (node (ref "C33") (pin "1") (pinfunction "1_1") (pintype "passive"))
      (node (ref "C35") (pin "1") (pinfunction "1_1") (pintype "passive"))
      (node (ref "C36") (pin "1") (pinfunction "1_1") (pintype "passive"))
      (node (ref "C9") (pin "1") (pinfunction "1_1") (pintype "passive"))
      (node (ref "F1") (pin "2") (pinfunction "2_2") (pintype "passive"))
      (node (ref "IC10") (pin "5") (pinfunction "VCC_5") (pintype "power_in"))
      (node (ref "IC12") (pin "1") (pinfunction "AVDD_1") (pintype "bidirectional"))
      (node (ref "IC13") (pin "1") (pinfunction "AVDD_1") (pintype "bidirectional"))
      (node (ref "IC14") (pin "1") (pinfunction "AVDD_1") (pintype "bidirectional"))
      (node (ref "IC15") (pin "1") (pinfunction "AVDD_1") (pintype "bidirectional"))
      (node (ref "IC16") (pin "1") (pinfunction "AVDD_1") (pintype "bidirectional"))
      (node (ref "IC17") (pin "1") (pinfunction "AVDD_1") (pintype "bidirectional"))
      (node (ref "IC18") (pin "5") (pinfunction "VCC_5") (pintype "power_in"))
      (node (ref "IC19") (pin "5") (pinfunction "VCC_5") (pintype "power_in"))
      (node (ref "IC3") (pin "4") (pinfunction "VCCIO_4") (pintype "power_in"))
      (node (ref "IC5") (pin "5") (pinfunction "OUT_5") (pintype "bidirectional"))
      (node (ref "LED1") (pin "A1") (pinfunction "A_A1") (pintype "passive"))
      (node (ref "LED1") (pin "A2") (pinfunction "A_A2") (pintype "passive"))
      (node (ref "LED2") (pin "A1") (pinfunction "A_A1") (pintype "passive"))
      (node (ref "LED2") (pin "A2") (pinfunction "A_A2") (pintype "passive"))
      (node (ref "LED3") (pin "A1") (pinfunction "A_A1") (pintype "passive"))
      (node (ref "LED3") (pin "A2") (pinfunction "A_A2") (pintype "passive"))
      (node (ref "LED4") (pin "A1") (pinfunction "A_A1") (pintype "passive"))
      (node (ref "LED4") (pin "A2") (pinfunction "A_A2") (pintype "passive"))
      (node (ref "LED5") (pin "A1") (pinfunction "A_A1") (pintype "passive"))
      (node (ref "LED5") (pin "A2") (pinfunction "A_A2") (pintype "passive"))
      (node (ref "R18") (pin "1") (pinfunction "1_1") (pintype "passive"))
      (node (ref "R55") (pin "2") (pinfunction "2_2") (pintype "passive"))
    )
    (net (code "2") (name "+3V3_u") (class "Default")
      (node (ref "C22") (pin "1") (pinfunction "1_1") (pintype "passive"))
      (node (ref "C27") (pin "1") (pinfunction "1_1") (pintype "passive"))
      (node (ref "C28") (pin "1") (pinfunction "1_1") (pintype "passive"))
      (node (ref "C29") (pin "1") (pinfunction "1_1") (pintype "passive"))
      (node (ref "C32") (pin "1") (pinfunction "1_1") (pintype "passive"))
      (node (ref "F1") (pin "1") (pinfunction "1_1") (pintype "passive"))
      (node (ref "IC6") (pin "19") (pinfunction "VCC_19") (pintype "power_in"))
      (node (ref "IC6") (pin "31") (pinfunction "VCC_31") (pintype "power_in"))
      (node (ref "IC6") (pin "39") (pinfunction "AVCC_39") (pintype "power_in"))
      (node (ref "IC6") (pin "9") (pinfunction "VCC_9") (pintype "power_in"))
      (node (ref "OSC1") (pin "P$4") (pinfunction "VDD_P$4") (pintype "passive"))
      (node (ref "PDI") (pin "2") (pinfunction "2_2") (pintype "passive"))
      (node (ref "R48") (pin "2") (pinfunction "2_2") (pintype "passive"))
      (node (ref "R50") (pin "2") (pinfunction "2_2") (pintype "passive"))
    )
    (net (code "3") (name "+5V") (class "Default")
      (node (ref "+5V_TP") (pin "TP") (pinfunction "TP_TP") (pintype "input"))
      (node (ref "C10") (pin "1") (pinfunction "1_1") (pintype "passive"))
      (node (ref "C23") (pin "1") (pinfunction "1_1") (pintype "passive"))
      (node (ref "C31") (pin "1") (pinfunction "1_1") (pintype "passive"))
      (node (ref "C34") (pin "1") (pinfunction "1_1") (pintype "passive"))
      (node (ref "C37") (pin "1") (pinfunction "1_1") (pintype "passive"))
      (node (ref "C38") (pin "1") (pinfunction "1_1") (pintype "passive"))
      (node (ref "IC11") (pin "1") (pinfunction "IN_1") (pintype "bidirectional"))
      (node (ref "IC11") (pin "3") (pinfunction "EN_3") (pintype "bidirectional"))
      (node (ref "IC4") (pin "7") (pinfunction "OUT_7") (pintype "bidirectional"))
      (node (ref "IC5") (pin "1") (pinfunction "IN_1") (pintype "bidirectional"))
      (node (ref "IC5") (pin "3") (pinfunction "EN_3") (pintype "bidirectional"))
      (node (ref "IC7") (pin "1") (pinfunction "OE_1") (pintype "input"))
      (node (ref "IC7") (pin "5") (pinfunction "VCC_5") (pintype "power_in"))
      (node (ref "IC8") (pin "1") (pinfunction "OE_1") (pintype "input"))
      (node (ref "IC8") (pin "5") (pinfunction "VCC_5") (pintype "power_in"))
      (node (ref "IC9") (pin "1") (pinfunction "OE_1") (pintype "input"))
      (node (ref "IC9") (pin "5") (pinfunction "VCC_5") (pintype "power_in"))
      (node (ref "R26") (pin "1") (pinfunction "1_1") (pintype "passive"))
      (node (ref "SV1") (pin "10") (pinfunction "10_10") (pintype "passive"))
    )
    (net (code "4") (name "/+5_USB") (class "Default")
      (node (ref "C39") (pin "+") (pinfunction "+_+") (pintype "passive"))
      (node (ref "C42") (pin "1") (pinfunction "1_1") (pintype "passive"))
      (node (ref "C5") (pin "1") (pinfunction "1_1") (pintype "passive"))
      (node (ref "C8") (pin "1") (pinfunction "1_1") (pintype "passive"))
      (node (ref "D1") (pin "2") (pinfunction "A_2") (pintype "passive"))
      (node (ref "IC3") (pin "20") (pinfunction "VCC_20") (pintype "power_in"))
      (node (ref "IC4") (pin "8") (pinfunction "IN1_8") (pintype "bidirectional"))
      (node (ref "L1") (pin "1") (pinfunction "1_1") (pintype "passive"))
      (node (ref "Q5") (pin "1") (pinfunction "S_1") (pintype "passive"))
      (node (ref "R17") (pin "2") (pinfunction "2_2") (pintype "passive"))
    )
    (net (code "5") (name "/5VUSB_INPUT") (class "Default")
      (node (ref "C3") (pin "1") (pinfunction "1_1") (pintype "passive"))
      (node (ref "IC2") (pin "P$5") (pinfunction "VBUS_P$5") (pintype "bidirectional"))
      (node (ref "L1") (pin "2") (pinfunction "2_2") (pintype "passive"))
      (node (ref "USB") (pin "P$1") (pinfunction "1_P$1") (pintype "bidirectional"))
    )
    (net (code "6") (name "/BAT_READ") (class "Default")
      (node (ref "IC6") (pin "41") (pinfunction "PA1/ADC1_41") (pintype "bidirectional"))
      (node (ref "R6") (pin "1") (pinfunction "1_1") (pintype "passive"))
    )
    (net (code "7") (name "/BAT_VOLTAGE") (class "Default")
      (node (ref "IC6") (pin "40") (pinfunction "PA0/ADC0/AREF_40") (pintype "bidirectional"))
      (node (ref "R4") (pin "2") (pinfunction "2_2") (pintype "passive"))
      (node (ref "R5") (pin "1") (pinfunction "1_1") (pintype "passive"))
    )
    (net (code "8") (name "/BLIGHT_EN") (class "Default")
      (node (ref "R12") (pin "1") (pinfunction "1_1") (pintype "passive"))
      (node (ref "SV1") (pin "1") (pinfunction "1_1") (pintype "passive"))
    )
    (net (code "9") (name "/BLIGHT_EN_UC") (class "Default")
      (node (ref "IC6") (pin "1") (pinfunction "PA5/ADC5_1") (pintype "bidirectional"))
      (node (ref "IC8") (pin "2") (pinfunction "I_2") (pintype "input"))
    )
    (net (code "10") (name "/BUTTON") (class "Default")
      (node (ref "C62") (pin "1") (pinfunction "1_1") (pintype "passive"))
      (node (ref "IC6") (pin "7") (pinfunction "PB3/ADC11/DAC1_7") (pintype "bidirectional"))
      (node (ref "R48") (pin "1") (pinfunction "1_1") (pintype "passive"))
      (node (ref "R9") (pin "2") (pinfunction "2_2") (pintype "passive"))
    )
    (net (code "11") (name "/CHARGE_ENABLE") (class "Default")
      (node (ref "IC6") (pin "5") (pinfunction "PB1/ADC9_5") (pintype "bidirectional"))
      (node (ref "Q4") (pin "2") (pinfunction "G_2") (pintype "passive"))
      (node (ref "R19") (pin "2") (pinfunction "2_2") (pintype "passive"))
    )
    (net (code "12") (name "/CLOCK_IN") (class "Default")
      (node (ref "CLKIN") (pin "4") (pinfunction "4_4") (pintype "passive"))
      (node (ref "IC18") (pin "2") (pinfunction "I_2") (pintype "input"))
      (node (ref "IC6") (pin "26") (pinfunction "~RXD1MISOPD6_26") (pintype "bidirectional"))
      (node (ref "R3") (pin "2") (pinfunction "2_2") (pintype "passive"))
    )
    (net (code "13") (name "/CLOCK_OUT") (class "Default")
      (node (ref "IC19") (pin "2") (pinfunction "I_2") (pintype "input"))
      (node (ref "IC6") (pin "27") (pinfunction "~~{TXD1SCKCLKOPD7}_27") (pintype "bidirectional"))
    )
    (net (code "14") (name "/CLOCK_OUT_ISO") (class "Default")
      (node (ref "IC12") (pin "2") (pinfunction "A1_IN_2") (pintype "bidirectional"))
      (node (ref "IC13") (pin "2") (pinfunction "A1_IN_2") (pintype "bidirectional"))
      (node (ref "IC14") (pin "2") (pinfunction "A1_IN_2") (pintype "bidirectional"))
      (node (ref "IC15") (pin "2") (pinfunction "A1_IN_2") (pintype "bidirectional"))
      (node (ref "IC16") (pin "2") (pinfunction "A1_IN_2") (pintype "bidirectional"))
      (node (ref "IC17") (pin "2") (pinfunction "A1_IN_2") (pintype "bidirectional"))
      (node (ref "IC18") (pin "4") (pinfunction "O_4") (pintype "tri_state"))
      (node (ref "IC19") (pin "4") (pinfunction "O_4") (pintype "tri_state"))
      (node (ref "IC7") (pin "2") (pinfunction "I_2") (pintype "input"))
    )
    (net (code "15") (name "/DEVICE_AT_0") (class "Default")
      (node (ref "IC12") (pin "3") (pinfunction "A2_OUT_3") (pintype "bidirectional"))
      (node (ref "IC6") (pin "16") (pinfunction "PC6/MISO/RXD1_16") (pintype "bidirectional"))
    )
    (net (code "16") (name "/DEVICE_AT_1") (class "Default")
      (node (ref "IC13") (pin "3") (pinfunction "A2_OUT_3") (pintype "bidirectional"))
      (node (ref "IC6") (pin "17") (pinfunction "PC7/SCK/TXD1/CLKO/EVO_17") (pintype "bidirectional"))
    )
    (net (code "17") (name "/DEVICE_AT_2") (class "Default")
      (node (ref "IC14") (pin "3") (pinfunction "A2_OUT_3") (pintype "bidirectional"))
      (node (ref "IC6") (pin "44") (pinfunction "PA4/ADC4_44") (pintype "bidirectional"))
    )
    (net (code "18") (name "/DEVICE_AT_3") (class "Default")
      (node (ref "IC15") (pin "3") (pinfunction "A2_OUT_3") (pintype "bidirectional"))
      (node (ref "IC6") (pin "36") (pinfunction "PR0/XTAL2_36") (pintype "bidirectional"))
    )
    (net (code "19") (name "/DEVICE_AT_4") (class "Default")
      (node (ref "IC16") (pin "3") (pinfunction "A2_OUT_3") (pintype "bidirectional"))
      (node (ref "IC6") (pin "42") (pinfunction "PA2/ADC2_42") (pintype "bidirectional"))
    )
    (net (code "20") (name "/DEVICE_AT_5") (class "Default")
      (node (ref "IC17") (pin "3") (pinfunction "A2_OUT_3") (pintype "bidirectional"))
      (node (ref "IC6") (pin "43") (pinfunction "PA3/ADC3_43") (pintype "bidirectional"))
    )
    (net (code "21") (name "/DISCHARGE_BAT") (class "Default")
      (node (ref "IC6") (pin "6") (pinfunction "PB2/ADC10/DAC0_6") (pintype "bidirectional"))
      (node (ref "R14") (pin "1") (pinfunction "1_1") (pintype "passive"))
    )
    (net (code "22") (name "/EN_CLOCK_IN") (class "Default")
      (node (ref "IC18") (pin "1") (pinfunction "OE_1") (pintype "input"))
      (node (ref "IC6") (pin "22") (pinfunction "~OC0CRXD0PD2_22") (pintype "bidirectional"))
      (node (ref "R54") (pin "1") (pinfunction "1_1") (pintype "passive"))
    )
    (net (code "23") (name "/EN_CLOCK_OUT") (class "Default")
      (node (ref "IC19") (pin "1") (pinfunction "OE_1") (pintype "input"))
      (node (ref "IC6") (pin "21") (pinfunction "~OC0BXCK0PD1_21") (pintype "bidirectional"))
      (node (ref "R55") (pin "1") (pinfunction "1_1") (pintype "passive"))
    )
    (net (code "24") (name "/FTDI_CTS") (class "Default")
      (node (ref "IC3") (pin "11") (pinfunction "~{CTS}_11") (pintype "input"))
      (node (ref "IC6") (pin "29") (pinfunction "~XCK0OC0BSCLPE1_29") (pintype "bidirectional"))
    )
    (net (code "25") (name "/FTDI_RTS") (class "Default")
      (node (ref "IC3") (pin "3") (pinfunction "~{RTS}_3") (pintype "output"))
      (node (ref "IC6") (pin "28") (pinfunction "~{OC0ASDAPE0}_28") (pintype "bidirectional"))
    )
    (net (code "26") (name "/FTDI_RXD") (class "Default")
      (node (ref "IC3") (pin "5") (pinfunction "RXD_5") (pintype "input"))
      (node (ref "IC6") (pin "33") (pinfunction "~TXD0OC0DPE3_33") (pintype "bidirectional"))
    )
    (net (code "27") (name "/FTDI_TXD") (class "Default")
      (node (ref "IC3") (pin "1") (pinfunction "TXD_1") (pintype "output"))
      (node (ref "IC6") (pin "32") (pinfunction "~RXD0OC0CPE2_32") (pintype "bidirectional"))
    )
    (net (code "28") (name "/IDC_CLOCK_OUT") (class "Default")
      (node (ref "R11") (pin "1") (pinfunction "1_1") (pintype "passive"))
      (node (ref "SV1") (pin "2") (pinfunction "2_2") (pintype "passive"))
    )
    (net (code "29") (name "/LED_CLK_0") (class "Default")
      (node (ref "IC6") (pin "10") (pinfunction "PC0/OC0A/SDA_10") (pintype "bidirectional"))
      (node (ref "R21") (pin "1") (pinfunction "1_1") (pintype "passive"))
    )
    (net (code "30") (name "/LED_CLK_1") (class "Default")
      (node (ref "IC6") (pin "3") (pinfunction "PA7/ADC7/AC0-OUT_3") (pintype "bidirectional"))
      (node (ref "R22") (pin "1") (pinfunction "1_1") (pintype "passive"))
    )
    (net (code "31") (name "/LED_CLK_2") (class "Default")
      (node (ref "IC6") (pin "14") (pinfunction "PC4/OC1A/#SS_14") (pintype "bidirectional"))
      (node (ref "R23") (pin "1") (pinfunction "1_1") (pintype "passive"))
    )
    (net (code "32") (name "/LED_CLK_3") (class "Default")
      (node (ref "IC6") (pin "11") (pinfunction "PC1/OC0B/XCK0/SCL_11") (pintype "bidirectional"))
      (node (ref "R27") (pin "1") (pinfunction "1_1") (pintype "passive"))
    )
    (net (code "33") (name "/LED_CLK_4") (class "Default")
      (node (ref "IC6") (pin "2") (pinfunction "PA6/ADC6_2") (pintype "bidirectional"))
      (node (ref "R28") (pin "1") (pinfunction "1_1") (pintype "passive"))
    )
    (net (code "34") (name "/LED_CLK_5") (class "Default")
      (node (ref "IC6") (pin "15") (pinfunction "PC5/OC1B/MOSI/XCK1_15") (pintype "bidirectional"))
      (node (ref "R29") (pin "1") (pinfunction "1_1") (pintype "passive"))
    )
    (net (code "35") (name "/LED_LOCK") (class "Default")
      (node (ref "IC6") (pin "24") (pinfunction "~{#SSPD4}_24") (pintype "bidirectional"))
      (node (ref "R24") (pin "1") (pinfunction "1_1") (pintype "passive"))
    )
    (net (code "36") (name "/LED_PWR") (class "Default")
      (node (ref "IC6") (pin "20") (pinfunction "~{OC0APD0}_20") (pintype "bidirectional"))
      (node (ref "R25") (pin "1") (pinfunction "1_1") (pintype "passive"))
    )
    (net (code "37") (name "/LED_REP") (class "Default")
      (node (ref "IC6") (pin "23") (pinfunction "~OC0DTXD0PD3_23") (pintype "bidirectional"))
      (node (ref "R30") (pin "1") (pinfunction "1_1") (pintype "passive"))
    )
    (net (code "38") (name "/PDI-CLK") (class "Default")
      (node (ref "C40") (pin "1") (pinfunction "1_1") (pintype "passive"))
      (node (ref "IC6") (pin "35") (pinfunction "RESET/PDI-CLK_35") (pintype "input"))
      (node (ref "PDI") (pin "5") (pinfunction "5_5") (pintype "passive"))
      (node (ref "R50") (pin "1") (pinfunction "1_1") (pintype "passive"))
    )
    (net (code "39") (name "/PDI-DATA") (class "Default")
      (node (ref "IC6") (pin "34") (pinfunction "PDI-DATA_34") (pintype "bidirectional"))
      (node (ref "PDI") (pin "1") (pinfunction "1_1") (pintype "passive"))
    )
    (net (code "40") (name "/PWR_GOOD") (class "Default")
      (node (ref "IC4") (pin "1") (pinfunction "STAT_1") (pintype "bidirectional"))
      (node (ref "IC6") (pin "4") (pinfunction "PB0/ADC8/AREF_4") (pintype "bidirectional"))
      (node (ref "R26") (pin "2") (pinfunction "2_2") (pintype "passive"))
    )
    (net (code "41") (name "/RX") (class "Default")
      (node (ref "IC10") (pin "2") (pinfunction "I_2") (pintype "input"))
      (node (ref "R16") (pin "1") (pinfunction "1_1") (pintype "passive"))
      (node (ref "SV1") (pin "6") (pinfunction "6_6") (pintype "passive"))
    )
    (net (code "42") (name "/STATE") (class "Default")
      (node (ref "IC6") (pin "25") (pinfunction "~XCK1MOSIPD5_25") (pintype "bidirectional"))
      (node (ref "R31") (pin "1") (pinfunction "1_1") (pintype "passive"))
    )
    (net (code "43") (name "/TX") (class "Default")
      (node (ref "R10") (pin "1") (pinfunction "1_1") (pintype "passive"))
      (node (ref "SV1") (pin "4") (pinfunction "4_4") (pintype "passive"))
    )
    (net (code "44") (name "/UC_RX") (class "Default")
      (node (ref "IC10") (pin "4") (pinfunction "O_4") (pintype "tri_state"))
      (node (ref "IC6") (pin "12") (pinfunction "PC2/OC0C/RXD0_12") (pintype "bidirectional"))
    )
    (net (code "45") (name "/UC_TX") (class "Default")
      (node (ref "IC6") (pin "13") (pinfunction "PC3/OC0D/TXD0_13") (pintype "bidirectional"))
      (node (ref "IC9") (pin "2") (pinfunction "I_2") (pintype "input"))
    )
    (net (code "46") (name "/V_BATT") (class "Default")
      (node (ref "BATEN") (pin "1") (pinfunction "1_1") (pintype "passive"))
      (node (ref "C41") (pin "1") (pinfunction "1_1") (pintype "passive"))
      (node (ref "D2") (pin "2") (pinfunction "A_2") (pintype "passive"))
      (node (ref "IC1") (pin "3") (pinfunction "VBAT_3") (pintype "bidirectional"))
      (node (ref "IC4") (pin "6") (pinfunction "IN2_6") (pintype "bidirectional"))
      (node (ref "Q1") (pin "1") (pinfunction "S_1") (pintype "passive"))
      (node (ref "R15") (pin "1") (pinfunction "1_1") (pintype "passive"))
      (node (ref "R7") (pin "1") (pinfunction "1_1") (pintype "passive"))
    )
    (net (code "47") (name "GND") (class "Default")
      (node (ref "BUTTON") (pin "1") (pinfunction "3_1") (pintype "passive"))
      (node (ref "C1") (pin "2") (pinfunction "2_2") (pintype "passive"))
      (node (ref "C10") (pin "2") (pinfunction "2_2") (pintype "passive"))
      (node (ref "C11") (pin "2") (pinfunction "2_2") (pintype "passive"))
      (node (ref "C12") (pin "2") (pinfunction "2_2") (pintype "passive"))
      (node (ref "C14") (pin "2") (pinfunction "2_2") (pintype "passive"))
      (node (ref "C16") (pin "2") (pinfunction "2_2") (pintype "passive"))
      (node (ref "C18") (pin "2") (pinfunction "2_2") (pintype "passive"))
      (node (ref "C2") (pin "2") (pinfunction "2_2") (pintype "passive"))
      (node (ref "C20") (pin "2") (pinfunction "2_2") (pintype "passive"))
      (node (ref "C22") (pin "2") (pinfunction "2_2") (pintype "passive"))
      (node (ref "C23") (pin "2") (pinfunction "2_2") (pintype "passive"))
      (node (ref "C24") (pin "2") (pinfunction "2_2") (pintype "passive"))
      (node (ref "C25") (pin "2") (pinfunction "2_2") (pintype "passive"))
      (node (ref "C27") (pin "2") (pinfunction "2_2") (pintype "passive"))
      (node (ref "C28") (pin "2") (pinfunction "2_2") (pintype "passive"))
      (node (ref "C29") (pin "2") (pinfunction "2_2") (pintype "passive"))
      (node (ref "C3") (pin "2") (pinfunction "2_2") (pintype "passive"))
      (node (ref "C30") (pin "2") (pinfunction "2_2") (pintype "passive"))
      (node (ref "C31") (pin "2") (pinfunction "2_2") (pintype "passive"))
      (node (ref "C32") (pin "2") (pinfunction "2_2") (pintype "passive"))
      (node (ref "C33") (pin "2") (pinfunction "2_2") (pintype "passive"))
      (node (ref "C34") (pin "2") (pinfunction "2_2") (pintype "passive"))
      (node (ref "C35") (pin "2") (pinfunction "2_2") (pintype "passive"))
      (node (ref "C36") (pin "2") (pinfunction "2_2") (pintype "passive"))
      (node (ref "C37") (pin "2") (pinfunction "2_2") (pintype "passive"))
      (node (ref "C38") (pin "2") (pinfunction "2_2") (pintype "passive"))
      (node (ref "C39") (pin "-") (pinfunction "-_-") (pintype "passive"))
      (node (ref "C4") (pin "2") (pinfunction "2_2") (pintype "passive"))
      (node (ref "C40") (pin "2") (pinfunction "2_2") (pintype "passive"))
      (node (ref "C41") (pin "2") (pinfunction "2_2") (pintype "passive"))
      (node (ref "C42") (pin "2") (pinfunction "2_2") (pintype "passive"))
      (node (ref "C5") (pin "2") (pinfunction "2_2") (pintype "passive"))
      (node (ref "C6") (pin "2") (pinfunction "2_2") (pintype "passive"))
      (node (ref "C62") (pin "2") (pinfunction "2_2") (pintype "passive"))
      (node (ref "C7") (pin "2") (pinfunction "2_2") (pintype "passive"))
      (node (ref "C8") (pin "2") (pinfunction "2_2") (pintype "passive"))
      (node (ref "C9") (pin "2") (pinfunction "2_2") (pintype "passive"))
      (node (ref "CLKIN") (pin "5") (pinfunction "5_5") (pintype "passive"))
      (node (ref "GND_TP0") (pin "TP") (pinfunction "TP_TP") (pintype "input"))
      (node (ref "GND_TP1") (pin "TP") (pinfunction "TP_TP") (pintype "input"))
      (node (ref "IC1") (pin "2") (pinfunction "VSS_2") (pintype "bidirectional"))
      (node (ref "IC10") (pin "1") (pinfunction "OE_1") (pintype "input"))
      (node (ref "IC10") (pin "3") (pinfunction "GND_3") (pintype "power_in"))
      (node (ref "IC11") (pin "2") (pinfunction "GND_2") (pintype "bidirectional"))
      (node (ref "IC12") (pin "4") (pinfunction "AGND_4") (pintype "bidirectional"))
      (node (ref "IC13") (pin "4") (pinfunction "AGND_4") (pintype "bidirectional"))
      (node (ref "IC14") (pin "4") (pinfunction "AGND_4") (pintype "bidirectional"))
      (node (ref "IC15") (pin "4") (pinfunction "AGND_4") (pintype "bidirectional"))
      (node (ref "IC16") (pin "4") (pinfunction "AGND_4") (pintype "bidirectional"))
      (node (ref "IC17") (pin "4") (pinfunction "AGND_4") (pintype "bidirectional"))
      (node (ref "IC18") (pin "3") (pinfunction "GND_3") (pintype "power_in"))
      (node (ref "IC19") (pin "3") (pinfunction "GND_3") (pintype "power_in"))
      (node (ref "IC2") (pin "P$2") (pinfunction "GND_P$2") (pintype "bidirectional"))
      (node (ref "IC3") (pin "18") (pinfunction "GND_18") (pintype "power_in"))
      (node (ref "IC3") (pin "21") (pinfunction "GND_21") (pintype "power_in"))
      (node (ref "IC3") (pin "25") (pinfunction "GND_25") (pintype "power_in"))
      (node (ref "IC3") (pin "26") (pinfunction "TEST_26") (pintype "input"))
      (node (ref "IC3") (pin "7") (pinfunction "GND_7") (pintype "power_in"))
      (node (ref "IC4") (pin "5") (pinfunction "GND_5") (pintype "bidirectional"))
      (node (ref "IC5") (pin "2") (pinfunction "GND_2") (pintype "bidirectional"))
      (node (ref "IC6") (pin "18") (pinfunction "GND_18") (pintype "power_in"))
      (node (ref "IC6") (pin "30") (pinfunction "GND_30") (pintype "power_in"))
      (node (ref "IC6") (pin "38") (pinfunction "GND_38") (pintype "power_in"))
      (node (ref "IC6") (pin "8") (pinfunction "GND_8") (pintype "power_in"))
      (node (ref "IC7") (pin "3") (pinfunction "GND_3") (pintype "power_in"))
      (node (ref "IC8") (pin "3") (pinfunction "GND_3") (pintype "power_in"))
      (node (ref "IC9") (pin "3") (pinfunction "GND_3") (pintype "power_in"))
      (node (ref "OSC1") (pin "P$2") (pinfunction "GND_P$2") (pintype "passive"))
      (node (ref "PDI") (pin "6") (pinfunction "6_6") (pintype "passive"))
      (node (ref "Q2") (pin "E") (pinfunction "E_E") (pintype "passive"))
      (node (ref "Q3") (pin "E") (pinfunction "E_E") (pintype "passive"))
      (node (ref "Q4") (pin "1") (pinfunction "S_1") (pintype "passive"))
      (node (ref "R1") (pin "2") (pinfunction "2_2") (pintype "passive"))
      (node (ref "R13") (pin "1") (pinfunction "1_1") (pintype "passive"))
      (node (ref "R16") (pin "2") (pinfunction "2_2") (pintype "passive"))
      (node (ref "R19") (pin "1") (pinfunction "1_1") (pintype "passive"))
      (node (ref "R20") (pin "1") (pinfunction "1_1") (pintype "passive"))
      (node (ref "R5") (pin "2") (pinfunction "2_2") (pintype "passive"))
      (node (ref "R54") (pin "2") (pinfunction "2_2") (pintype "passive"))
      (node (ref "R_I_MAX") (pin "2") (pinfunction "2_2") (pintype "passive"))
      (node (ref "SV1") (pin "9") (pinfunction "9_9") (pintype "passive"))
      (node (ref "T1") (pin "2") (pinfunction "E_2") (pintype "passive"))
      (node (ref "T10") (pin "2") (pinfunction "E_2") (pintype "passive"))
      (node (ref "T2") (pin "2") (pinfunction "E_2") (pintype "passive"))
      (node (ref "T3") (pin "2") (pinfunction "E_2") (pintype "passive"))
      (node (ref "T4") (pin "2") (pinfunction "E_2") (pintype "passive"))
      (node (ref "T5") (pin "2") (pinfunction "E_2") (pintype "passive"))
      (node (ref "T6") (pin "2") (pinfunction "E_2") (pintype "passive"))
      (node (ref "T7") (pin "2") (pinfunction "E_2") (pintype "passive"))
      (node (ref "T8") (pin "2") (pinfunction "E_2") (pintype "passive"))
      (node (ref "T9") (pin "2") (pinfunction "E_2") (pintype "passive"))
      (node (ref "USB") (pin "P$5") (pinfunction "5_P$5") (pintype "bidirectional"))
      (node (ref "X1") (pin "2") (pinfunction "S_2") (pintype "passive"))
    )
    (net (code "48") (name "Net-(BUTTON-Pad2)") (class "Default")
      (node (ref "BUTTON") (pin "2") (pinfunction "2_2") (pintype "passive"))
      (node (ref "R9") (pin "1") (pinfunction "1_1") (pintype "passive"))
    )
    (net (code "49") (name "Net-(CLKIN-Pad1)") (class "Default")
      (node (ref "CLKIN") (pin "1") (pinfunction "1_1") (pintype "passive"))
      (node (ref "R2") (pin "2") (pinfunction "2_2") (pintype "passive"))
      (node (ref "R3") (pin "1") (pinfunction "1_1") (pintype "passive"))
    )
    (net (code "50") (name "Net-(D1-C)") (class "Default")
      (node (ref "D1") (pin "1") (pinfunction "C_1") (pintype "passive"))
      (node (ref "D2") (pin "1") (pinfunction "C_1") (pintype "passive"))
      (node (ref "IC4") (pin "2") (pinfunction "D0_2") (pintype "bidirectional"))
    )
    (net (code "51") (name "Net-(IC1-PROG)") (class "Default")
      (node (ref "IC1") (pin "5") (pinfunction "PROG_5") (pintype "bidirectional"))
      (node (ref "R13") (pin "2") (pinfunction "2_2") (pintype "passive"))
    )
    (net (code "52") (name "Net-(IC1-VDD)") (class "Default")
      (node (ref "IC1") (pin "4") (pinfunction "VDD_4") (pintype "bidirectional"))
      (node (ref "Q5") (pin "3") (pinfunction "D_3") (pintype "passive"))
    )
    (net (code "53") (name "Net-(IC3-3V3OUT)") (class "Default")
      (node (ref "C7") (pin "1") (pinfunction "1_1") (pintype "passive"))
      (node (ref "IC3") (pin "17") (pinfunction "3V3OUT_17") (pintype "output"))
    )
    (net (code "54") (name "Net-(IC3-USBDM)") (class "Default")
      (node (ref "C6") (pin "1") (pinfunction "1_1") (pintype "passive"))
      (node (ref "IC2") (pin "P$6") (pinfunction "IO1_P$6") (pintype "bidirectional"))
      (node (ref "IC3") (pin "16") (pinfunction "USBDM_16") (pintype "bidirectional"))
    )
    (net (code "55") (name "Net-(IC3-USBDP)") (class "Default")
      (node (ref "C4") (pin "1") (pinfunction "1_1") (pintype "passive"))
      (node (ref "IC2") (pin "P$4") (pinfunction "IO2_P$4") (pintype "bidirectional"))
      (node (ref "IC3") (pin "15") (pinfunction "USBDP_15") (pintype "bidirectional"))
    )
    (net (code "56") (name "Net-(IC3-~{RESET})") (class "Default")
      (node (ref "IC3") (pin "19") (pinfunction "~{RESET}_19") (pintype "input"))
      (node (ref "R18") (pin "2") (pinfunction "2_2") (pintype "passive"))
    )
    (net (code "57") (name "Net-(IC4-D1)") (class "Default")
      (node (ref "IC4") (pin "3") (pinfunction "D1_3") (pintype "bidirectional"))
      (node (ref "R20") (pin "2") (pinfunction "2_2") (pintype "passive"))
    )
    (net (code "58") (name "Net-(IC4-ILIM)") (class "Default")
      (node (ref "IC4") (pin "4") (pinfunction "ILIM_4") (pintype "bidirectional"))
      (node (ref "R_I_MAX") (pin "1") (pinfunction "1_1") (pintype "passive"))
    )
    (net (code "59") (name "Net-(IC6-PR1{slash}XTAL1)") (class "Default")
      (node (ref "IC6") (pin "37") (pinfunction "PR1/XTAL1_37") (pintype "bidirectional"))
      (node (ref "OSC1") (pin "P$3") (pinfunction "OUTPUT_P$3") (pintype "passive"))
    )
    (net (code "60") (name "Net-(IC7A-O)") (class "Default")
      (node (ref "IC7") (pin "4") (pinfunction "O_4") (pintype "output"))
      (node (ref "R11") (pin "2") (pinfunction "2_2") (pintype "passive"))
    )
    (net (code "61") (name "Net-(IC8A-O)") (class "Default")
      (node (ref "IC8") (pin "4") (pinfunction "O_4") (pintype "output"))
      (node (ref "R12") (pin "2") (pinfunction "2_2") (pintype "passive"))
    )
    (net (code "62") (name "Net-(IC9A-O)") (class "Default")
      (node (ref "IC9") (pin "4") (pinfunction "O_4") (pintype "output"))
      (node (ref "R10") (pin "2") (pinfunction "2_2") (pintype "passive"))
    )
    (net (code "63") (name "Net-(IC11-OUT)") (class "Default")
      (node (ref "C24") (pin "1") (pinfunction "1_1") (pintype "passive"))
      (node (ref "IC11") (pin "5") (pinfunction "OUT_5") (pintype "bidirectional"))
      (node (ref "R2") (pin "1") (pinfunction "1_1") (pintype "passive"))
    )
    (net (code "64") (name "Net-(IC12-B1_OUT)") (class "Default")
      (node (ref "CLKOUT0") (pin "4") (pinfunction "4_4") (pintype "passive"))
      (node (ref "IC12") (pin "7") (pinfunction "B1_OUT_7") (pintype "bidirectional"))
    )
    (net (code "65") (name "Net-(IC12-B2_IN)") (class "Default")
      (node (ref "C26") (pin "1") (pinfunction "1_1") (pintype "passive"))
      (node (ref "CLKOUT0") (pin "1") (pinfunction "1_1") (pintype "passive"))
      (node (ref "IC12") (pin "6") (pinfunction "B2_IN_6") (pintype "bidirectional"))
      (node (ref "IC12") (pin "8") (pinfunction "BVDD_8") (pintype "bidirectional"))
    )
    (net (code "66") (name "Net-(IC12-BGND)") (class "Default")
      (node (ref "C26") (pin "2") (pinfunction "2_2") (pintype "passive"))
      (node (ref "CLKOUT0") (pin "5") (pinfunction "5_5") (pintype "passive"))
      (node (ref "IC12") (pin "5") (pinfunction "BGND_5") (pintype "bidirectional"))
    )
    (net (code "67") (name "Net-(IC13-B1_OUT)") (class "Default")
      (node (ref "CLKOUT1") (pin "4") (pinfunction "4_4") (pintype "passive"))
      (node (ref "IC13") (pin "7") (pinfunction "B1_OUT_7") (pintype "bidirectional"))
    )
    (net (code "68") (name "Net-(IC13-B2_IN)") (class "Default")
      (node (ref "C13") (pin "1") (pinfunction "1_1") (pintype "passive"))
      (node (ref "CLKOUT1") (pin "1") (pinfunction "1_1") (pintype "passive"))
      (node (ref "IC13") (pin "6") (pinfunction "B2_IN_6") (pintype "bidirectional"))
      (node (ref "IC13") (pin "8") (pinfunction "BVDD_8") (pintype "bidirectional"))
    )
    (net (code "69") (name "Net-(IC13-BGND)") (class "Default")
      (node (ref "C13") (pin "2") (pinfunction "2_2") (pintype "passive"))
      (node (ref "CLKOUT1") (pin "5") (pinfunction "5_5") (pintype "passive"))
      (node (ref "IC13") (pin "5") (pinfunction "BGND_5") (pintype "bidirectional"))
    )
    (net (code "70") (name "Net-(IC14-B1_OUT)") (class "Default")
      (node (ref "CLKOUT2") (pin "4") (pinfunction "4_4") (pintype "passive"))
      (node (ref "IC14") (pin "7") (pinfunction "B1_OUT_7") (pintype "bidirectional"))
    )
    (net (code "71") (name "Net-(IC14-B2_IN)") (class "Default")
      (node (ref "C15") (pin "1") (pinfunction "1_1") (pintype "passive"))
      (node (ref "CLKOUT2") (pin "1") (pinfunction "1_1") (pintype "passive"))
      (node (ref "IC14") (pin "6") (pinfunction "B2_IN_6") (pintype "bidirectional"))
      (node (ref "IC14") (pin "8") (pinfunction "BVDD_8") (pintype "bidirectional"))
    )
    (net (code "72") (name "Net-(IC14-BGND)") (class "Default")
      (node (ref "C15") (pin "2") (pinfunction "2_2") (pintype "passive"))
      (node (ref "CLKOUT2") (pin "5") (pinfunction "5_5") (pintype "passive"))
      (node (ref "IC14") (pin "5") (pinfunction "BGND_5") (pintype "bidirectional"))
    )
    (net (code "73") (name "Net-(IC15-B1_OUT)") (class "Default")
      (node (ref "CLKOUT3") (pin "4") (pinfunction "4_4") (pintype "passive"))
      (node (ref "IC15") (pin "7") (pinfunction "B1_OUT_7") (pintype "bidirectional"))
    )
    (net (code "74") (name "Net-(IC15-B2_IN)") (class "Default")
      (node (ref "C17") (pin "1") (pinfunction "1_1") (pintype "passive"))
      (node (ref "CLKOUT3") (pin "1") (pinfunction "1_1") (pintype "passive"))
      (node (ref "IC15") (pin "6") (pinfunction "B2_IN_6") (pintype "bidirectional"))
      (node (ref "IC15") (pin "8") (pinfunction "BVDD_8") (pintype "bidirectional"))
    )
    (net (code "75") (name "Net-(IC15-BGND)") (class "Default")
      (node (ref "C17") (pin "2") (pinfunction "2_2") (pintype "passive"))
      (node (ref "CLKOUT3") (pin "5") (pinfunction "5_5") (pintype "passive"))
      (node (ref "IC15") (pin "5") (pinfunction "BGND_5") (pintype "bidirectional"))
    )
    (net (code "76") (name "Net-(IC16-B1_OUT)") (class "Default")
      (node (ref "CLKOUT4") (pin "4") (pinfunction "4_4") (pintype "passive"))
      (node (ref "IC16") (pin "7") (pinfunction "B1_OUT_7") (pintype "bidirectional"))
    )
    (net (code "77") (name "Net-(IC16-B2_IN)") (class "Default")
      (node (ref "C19") (pin "1") (pinfunction "1_1") (pintype "passive"))
      (node (ref "CLKOUT4") (pin "1") (pinfunction "1_1") (pintype "passive"))
      (node (ref "IC16") (pin "6") (pinfunction "B2_IN_6") (pintype "bidirectional"))
      (node (ref "IC16") (pin "8") (pinfunction "BVDD_8") (pintype "bidirectional"))
    )
    (net (code "78") (name "Net-(IC16-BGND)") (class "Default")
      (node (ref "C19") (pin "2") (pinfunction "2_2") (pintype "passive"))
      (node (ref "CLKOUT4") (pin "5") (pinfunction "5_5") (pintype "passive"))
      (node (ref "IC16") (pin "5") (pinfunction "BGND_5") (pintype "bidirectional"))
    )
    (net (code "79") (name "Net-(IC17-B1_OUT)") (class "Default")
      (node (ref "CLKOUT5") (pin "4") (pinfunction "4_4") (pintype "passive"))
      (node (ref "IC17") (pin "7") (pinfunction "B1_OUT_7") (pintype "bidirectional"))
    )
    (net (code "80") (name "Net-(IC17-B2_IN)") (class "Default")
      (node (ref "C21") (pin "1") (pinfunction "1_1") (pintype "passive"))
      (node (ref "CLKOUT5") (pin "1") (pinfunction "1_1") (pintype "passive"))
      (node (ref "IC17") (pin "6") (pinfunction "B2_IN_6") (pintype "bidirectional"))
      (node (ref "IC17") (pin "8") (pinfunction "BVDD_8") (pintype "bidirectional"))
    )
    (net (code "81") (name "Net-(IC17-BGND)") (class "Default")
      (node (ref "C21") (pin "2") (pinfunction "2_2") (pintype "passive"))
      (node (ref "CLKOUT5") (pin "5") (pinfunction "5_5") (pintype "passive"))
      (node (ref "IC17") (pin "5") (pinfunction "BGND_5") (pintype "bidirectional"))
    )
    (net (code "82") (name "Net-(LED1A-C)") (class "Default")
      (node (ref "LED1") (pin "C1") (pinfunction "C_C1") (pintype "passive"))
      (node (ref "R40") (pin "1") (pinfunction "1_1") (pintype "passive"))
    )
    (net (code "83") (name "Net-(LED1B-C)") (class "Default")
      (node (ref "LED1") (pin "C2") (pinfunction "C_C2") (pintype "passive"))
      (node (ref "R33") (pin "1") (pinfunction "1_1") (pintype "passive"))
    )
    (net (code "84") (name "Net-(LED2A-C)") (class "Default")
      (node (ref "LED2") (pin "C1") (pinfunction "C_C1") (pintype "passive"))
      (node (ref "R41") (pin "1") (pinfunction "1_1") (pintype "passive"))
    )
    (net (code "85") (name "Net-(LED2B-C)") (class "Default")
      (node (ref "LED2") (pin "C2") (pinfunction "C_C2") (pintype "passive"))
      (node (ref "R34") (pin "1") (pinfunction "1_1") (pintype "passive"))
    )
    (net (code "86") (name "Net-(LED3A-C)") (class "Default")
      (node (ref "LED3") (pin "C1") (pinfunction "C_C1") (pintype "passive"))
      (node (ref "R42") (pin "1") (pinfunction "1_1") (pintype "passive"))
    )
    (net (code "87") (name "Net-(LED3B-C)") (class "Default")
      (node (ref "LED3") (pin "C2") (pinfunction "C_C2") (pintype "passive"))
      (node (ref "R35") (pin "1") (pinfunction "1_1") (pintype "passive"))
    )
    (net (code "88") (name "Net-(LED4A-C)") (class "Default")
      (node (ref "LED4") (pin "C1") (pinfunction "C_C1") (pintype "passive"))
      (node (ref "R44") (pin "1") (pinfunction "1_1") (pintype "passive"))
    )
    (net (code "89") (name "Net-(LED4B-C)") (class "Default")
      (node (ref "LED4") (pin "C2") (pinfunction "C_C2") (pintype "passive"))
      (node (ref "R36") (pin "1") (pinfunction "1_1") (pintype "passive"))
    )
    (net (code "90") (name "Net-(LED5A-C)") (class "Default")
      (node (ref "LED5") (pin "C1") (pinfunction "C_C1") (pintype "passive"))
      (node (ref "R45") (pin "1") (pinfunction "1_1") (pintype "passive"))
    )
    (net (code "91") (name "Net-(LED5B-C)") (class "Default")
      (node (ref "LED5") (pin "C2") (pinfunction "C_C2") (pintype "passive"))
      (node (ref "R37") (pin "1") (pinfunction "1_1") (pintype "passive"))
    )
    (net (code "92") (name "Net-(Q1-D)") (class "Default")
      (node (ref "Q1") (pin "3") (pinfunction "D_3") (pintype "passive"))
      (node (ref "R4") (pin "1") (pinfunction "1_1") (pintype "passive"))
    )
    (net (code "93") (name "Net-(Q1-G)") (class "Default")
      (node (ref "Q1") (pin "2") (pinfunction "G_2") (pintype "passive"))
      (node (ref "Q2") (pin "C") (pinfunction "C_C") (pintype "passive"))
      (node (ref "R7") (pin "2") (pinfunction "2_2") (pintype "passive"))
    )
    (net (code "94") (name "Net-(Q2-PadB)") (class "Default")
      (node (ref "Q2") (pin "B") (pinfunction "B_B") (pintype "passive"))
      (node (ref "R6") (pin "2") (pinfunction "2_2") (pintype "passive"))
    )
    (net (code "95") (name "Net-(Q3-PadB)") (class "Default")
      (node (ref "Q3") (pin "B") (pinfunction "B_B") (pintype "passive"))
      (node (ref "R14") (pin "2") (pinfunction "2_2") (pintype "passive"))
    )
    (net (code "96") (name "Net-(Q3-PadC)") (class "Default")
      (node (ref "Q3") (pin "C") (pinfunction "C_C") (pintype "passive"))
      (node (ref "R15") (pin "2") (pinfunction "2_2") (pintype "passive"))
    )
    (net (code "97") (name "Net-(Q4-D)") (class "Default")
      (node (ref "Q4") (pin "3") (pinfunction "D_3") (pintype "passive"))
      (node (ref "Q5") (pin "2") (pinfunction "G_2") (pintype "passive"))
      (node (ref "R17") (pin "1") (pinfunction "1_1") (pintype "passive"))
    )
    (net (code "98") (name "Net-(T1-B)") (class "Default")
      (node (ref "R21") (pin "2") (pinfunction "2_2") (pintype "passive"))
      (node (ref "T1") (pin "1") (pinfunction "B_1") (pintype "passive"))
    )
    (net (code "99") (name "Net-(T1-C)") (class "Default")
      (node (ref "R33") (pin "2") (pinfunction "2_2") (pintype "passive"))
      (node (ref "T1") (pin "3") (pinfunction "C_3") (pintype "passive"))
    )
    (net (code "100") (name "Net-(T2-B)") (class "Default")
      (node (ref "R27") (pin "2") (pinfunction "2_2") (pintype "passive"))
      (node (ref "T2") (pin "1") (pinfunction "B_1") (pintype "passive"))
    )
    (net (code "101") (name "Net-(T2-C)") (class "Default")
      (node (ref "R40") (pin "2") (pinfunction "2_2") (pintype "passive"))
      (node (ref "T2") (pin "3") (pinfunction "C_3") (pintype "passive"))
    )
    (net (code "102") (name "Net-(T3-B)") (class "Default")
      (node (ref "R22") (pin "2") (pinfunction "2_2") (pintype "passive"))
      (node (ref "T3") (pin "1") (pinfunction "B_1") (pintype "passive"))
    )
    (net (code "103") (name "Net-(T3-C)") (class "Default")
      (node (ref "R34") (pin "2") (pinfunction "2_2") (pintype "passive"))
      (node (ref "T3") (pin "3") (pinfunction "C_3") (pintype "passive"))
    )
    (net (code "104") (name "Net-(T4-B)") (class "Default")
      (node (ref "R28") (pin "2") (pinfunction "2_2") (pintype "passive"))
      (node (ref "T4") (pin "1") (pinfunction "B_1") (pintype "passive"))
    )
    (net (code "105") (name "Net-(T4-C)") (class "Default")
      (node (ref "R41") (pin "2") (pinfunction "2_2") (pintype "passive"))
      (node (ref "T4") (pin "3") (pinfunction "C_3") (pintype "passive"))
    )
    (net (code "106") (name "Net-(T5-B)") (class "Default")
      (node (ref "R23") (pin "2") (pinfunction "2_2") (pintype "passive"))
      (node (ref "T5") (pin "1") (pinfunction "B_1") (pintype "passive"))
    )
    (net (code "107") (name "Net-(T5-C)") (class "Default")
      (node (ref "R35") (pin "2") (pinfunction "2_2") (pintype "passive"))
      (node (ref "T5") (pin "3") (pinfunction "C_3") (pintype "passive"))
    )
    (net (code "108") (name "Net-(T6-B)") (class "Default")
      (node (ref "R29") (pin "2") (pinfunction "2_2") (pintype "passive"))
      (node (ref "T6") (pin "1") (pinfunction "B_1") (pintype "passive"))
    )
    (net (code "109") (name "Net-(T6-C)") (class "Default")
      (node (ref "R42") (pin "2") (pinfunction "2_2") (pintype "passive"))
      (node (ref "T6") (pin "3") (pinfunction "C_3") (pintype "passive"))
    )
    (net (code "110") (name "Net-(T7-B)") (class "Default")
      (node (ref "R24") (pin "2") (pinfunction "2_2") (pintype "passive"))
      (node (ref "T7") (pin "1") (pinfunction "B_1") (pintype "passive"))
    )
    (net (code "111") (name "Net-(T7-C)") (class "Default")
      (node (ref "R36") (pin "2") (pinfunction "2_2") (pintype "passive"))
      (node (ref "T7") (pin "3") (pinfunction "C_3") (pintype "passive"))
    )
    (net (code "112") (name "Net-(T8-B)") (class "Default")
      (node (ref "R30") (pin "2") (pinfunction "2_2") (pintype "passive"))
      (node (ref "T8") (pin "1") (pinfunction "B_1") (pintype "passive"))
    )
    (net (code "113") (name "Net-(T8-C)") (class "Default")
      (node (ref "R44") (pin "2") (pinfunction "2_2") (pintype "passive"))
      (node (ref "T8") (pin "3") (pinfunction "C_3") (pintype "passive"))
    )
    (net (code "114") (name "Net-(T9-B)") (class "Default")
      (node (ref "R25") (pin "2") (pinfunction "2_2") (pintype "passive"))
      (node (ref "T9") (pin "1") (pinfunction "B_1") (pintype "passive"))
    )
    (net (code "115") (name "Net-(T9-C)") (class "Default")
      (node (ref "R37") (pin "2") (pinfunction "2_2") (pintype "passive"))
      (node (ref "T9") (pin "3") (pinfunction "C_3") (pintype "passive"))
    )
    (net (code "116") (name "Net-(T10-B)") (class "Default")
      (node (ref "R31") (pin "2") (pinfunction "2_2") (pintype "passive"))
      (node (ref "T10") (pin "1") (pinfunction "B_1") (pintype "passive"))
    )
    (net (code "117") (name "Net-(T10-C)") (class "Default")
      (node (ref "R45") (pin "2") (pinfunction "2_2") (pintype "passive"))
      (node (ref "T10") (pin "3") (pinfunction "C_3") (pintype "passive"))
    )
    (net (code "118") (name "Net-(USB-2)") (class "Default")
      (node (ref "IC2") (pin "P$1") (pinfunction "IO1_P$1") (pintype "bidirectional"))
      (node (ref "USB") (pin "P$2") (pinfunction "2_P$2") (pintype "bidirectional"))
    )
    (net (code "119") (name "Net-(USB-3)") (class "Default")
      (node (ref "IC2") (pin "P$3") (pinfunction "IO2_P$3") (pintype "bidirectional"))
      (node (ref "USB") (pin "P$3") (pinfunction "3_P$3") (pintype "bidirectional"))
    )
    (net (code "120") (name "Net-(USB-P$1)") (class "Default")
      (node (ref "R1") (pin "1") (pinfunction "1_1") (pintype "passive"))
      (node (ref "USB") (pin "SHIELD_1") (pinfunction "P$1_SHIELD_1") (pintype "bidirectional"))
    )
    (net (code "121") (name "Net-(USB-P$4)") (class "Default")
      (node (ref "C2") (pin "1") (pinfunction "1_1") (pintype "passive"))
      (node (ref "USB") (pin "SHIELD_4") (pinfunction "P$4_SHIELD_4") (pintype "bidirectional"))
    )
    (net (code "122") (name "Net-(X1A-S)") (class "Default")
      (node (ref "BATEN") (pin "2") (pinfunction "2_2") (pintype "passive"))
      (node (ref "BAT_TP") (pin "TP") (pinfunction "TP_TP") (pintype "input"))
      (node (ref "X1") (pin "1") (pinfunction "S_1") (pintype "passive"))
    )
    (net (code "123") (name "unconnected-(BATEN-Pad3)") (class "Default")
      (node (ref "BATEN") (pin "3") (pinfunction "3_3") (pintype "passive"))
    )
    (net (code "124") (name "unconnected-(BUTTON-1-Pad3)") (class "Default")
      (node (ref "BUTTON") (pin "3") (pinfunction "1_3") (pintype "passive"))
    )
    (net (code "125") (name "unconnected-(IC1-STAT-Pad1)") (class "Default")
      (node (ref "IC1") (pin "1") (pinfunction "STAT_1") (pintype "bidirectional"))
    )
    (net (code "126") (name "unconnected-(IC3-CBUS0-Pad23)") (class "Default")
      (node (ref "IC3") (pin "23") (pinfunction "CBUS0_23") (pintype "bidirectional"))
    )
    (net (code "127") (name "unconnected-(IC3-CBUS1-Pad22)") (class "Default")
      (node (ref "IC3") (pin "22") (pinfunction "CBUS1_22") (pintype "bidirectional"))
    )
    (net (code "128") (name "unconnected-(IC3-CBUS2-Pad13)") (class "Default")
      (node (ref "IC3") (pin "13") (pinfunction "CBUS2_13") (pintype "bidirectional"))
    )
    (net (code "129") (name "unconnected-(IC3-CBUS3-Pad14)") (class "Default")
      (node (ref "IC3") (pin "14") (pinfunction "CBUS3_14") (pintype "bidirectional"))
    )
    (net (code "130") (name "unconnected-(IC3-CBUS4-Pad12)") (class "Default")
      (node (ref "IC3") (pin "12") (pinfunction "CBUS4_12") (pintype "bidirectional"))
    )
    (net (code "131") (name "unconnected-(IC3-OSCI-Pad27)") (class "Default")
      (node (ref "IC3") (pin "27") (pinfunction "OSCI_27") (pintype "input"))
    )
    (net (code "132") (name "unconnected-(IC3-OSCO-Pad28)") (class "Default")
      (node (ref "IC3") (pin "28") (pinfunction "OSCO_28") (pintype "output"))
    )
    (net (code "133") (name "unconnected-(IC3-~{DCD}-Pad10)") (class "Default")
      (node (ref "IC3") (pin "10") (pinfunction "~{DCD}_10") (pintype "input"))
    )
    (net (code "134") (name "unconnected-(IC3-~{DSR}-Pad9)") (class "Default")
      (node (ref "IC3") (pin "9") (pinfunction "~{DSR}_9") (pintype "input"))
    )
    (net (code "135") (name "unconnected-(IC3-~{DTR}-Pad2)") (class "Default")
      (node (ref "IC3") (pin "2") (pinfunction "~{DTR}_2") (pintype "output"))
    )
    (net (code "136") (name "unconnected-(IC3-~{RI}-Pad6)") (class "Default")
      (node (ref "IC3") (pin "6") (pinfunction "~{RI}_6") (pintype "input"))
    )
    (net (code "137") (name "unconnected-(IC5-N{slash}C-Pad4)") (class "Default")
      (node (ref "IC5") (pin "4") (pinfunction "N/C_4") (pintype "bidirectional"))
    )
    (net (code "138") (name "unconnected-(IC11-N{slash}C-Pad4)") (class "Default")
      (node (ref "IC11") (pin "4") (pinfunction "N/C_4") (pintype "bidirectional"))
    )
    (net (code "139") (name "unconnected-(OSC1-STANDBY#-PadP$1)") (class "Default")
      (node (ref "OSC1") (pin "P$1") (pinfunction "STANDBY#_P$1") (pintype "passive"))
    )
    (net (code "140") (name "unconnected-(PDI-Pad3)") (class "Default")
      (node (ref "PDI") (pin "3") (pinfunction "3_3") (pintype "passive"))
    )
    (net (code "141") (name "unconnected-(PDI-Pad4)") (class "Default")
      (node (ref "PDI") (pin "4") (pinfunction "4_4") (pintype "passive"))
    )
    (net (code "142") (name "unconnected-(SV1-Pad3)") (class "Default")
      (node (ref "SV1") (pin "3") (pinfunction "3_3") (pintype "passive"))
    )
    (net (code "143") (name "unconnected-(SV1-Pad5)") (class "Default")
      (node (ref "SV1") (pin "5") (pinfunction "5_5") (pintype "passive"))
    )
    (net (code "144") (name "unconnected-(SV1-Pad7)") (class "Default")
      (node (ref "SV1") (pin "7") (pinfunction "7_7") (pintype "passive"))
    )
    (net (code "145") (name "unconnected-(SV1-Pad8)") (class "Default")
      (node (ref "SV1") (pin "8") (pinfunction "8_8") (pintype "passive"))
    )
    (net (code "146") (name "unconnected-(USB-4-PadP$4)") (class "Default")
      (node (ref "USB") (pin "P$4") (pinfunction "4_P$4") (pintype "bidirectional"))
    )
    (net (code "147") (name "unconnected-(USB-P$2-PadSHIELD_2)") (class "Default")
      (node (ref "USB") (pin "SHIELD_2") (pinfunction "P$2_SHIELD_2") (pintype "bidirectional"))
    )
    (net (code "148") (name "unconnected-(USB-P$3-PadSHIELD_3)") (class "Default")
      (node (ref "USB") (pin "SHIELD_3") (pinfunction "P$3_SHIELD_3") (pintype "bidirectional"))
    )
  )
)
